# veils_v110.net
KiCad netlist of a schematic drawn in EAGLE
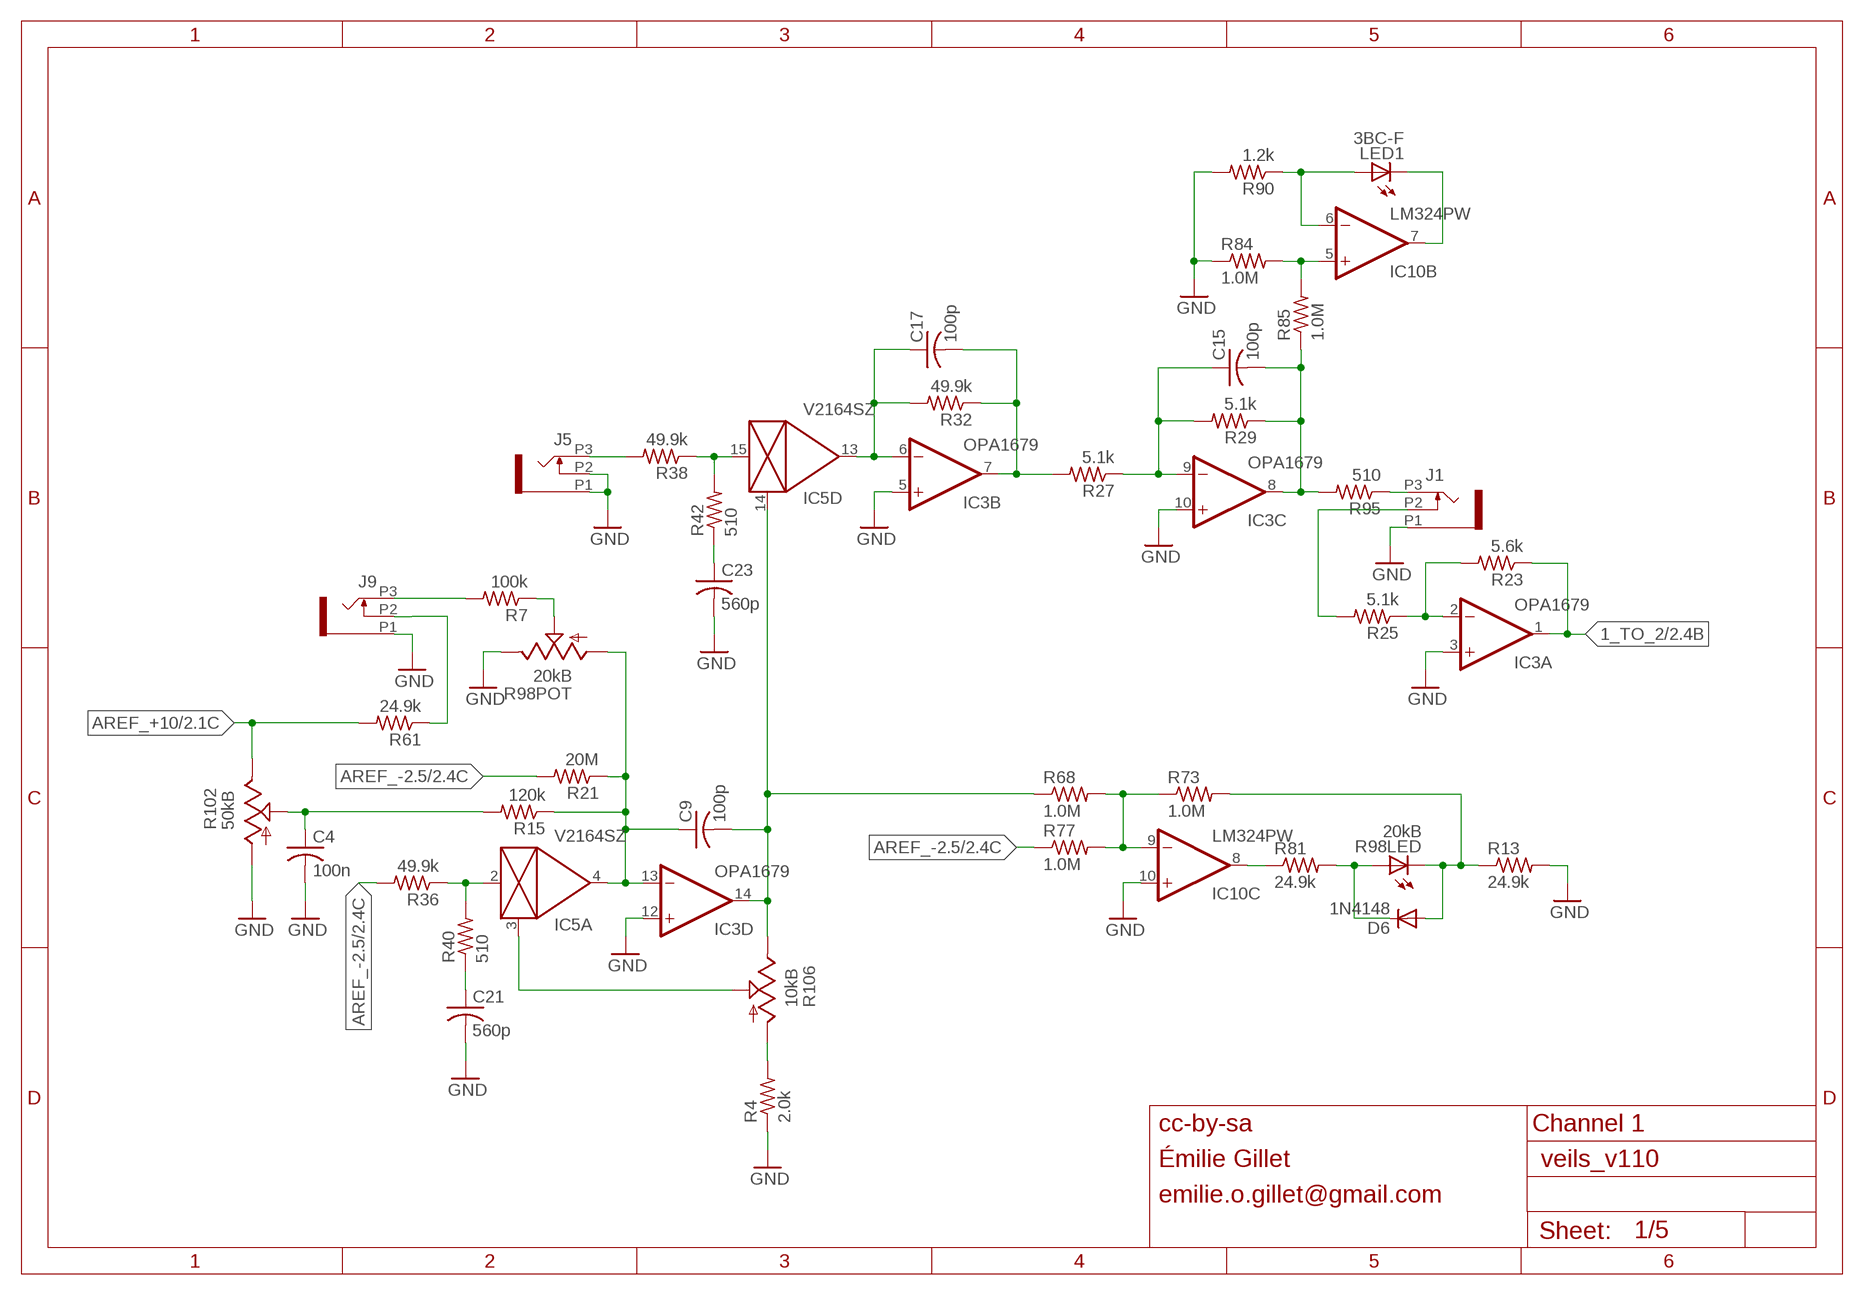
[diagram p0: schematic, sheet 1]
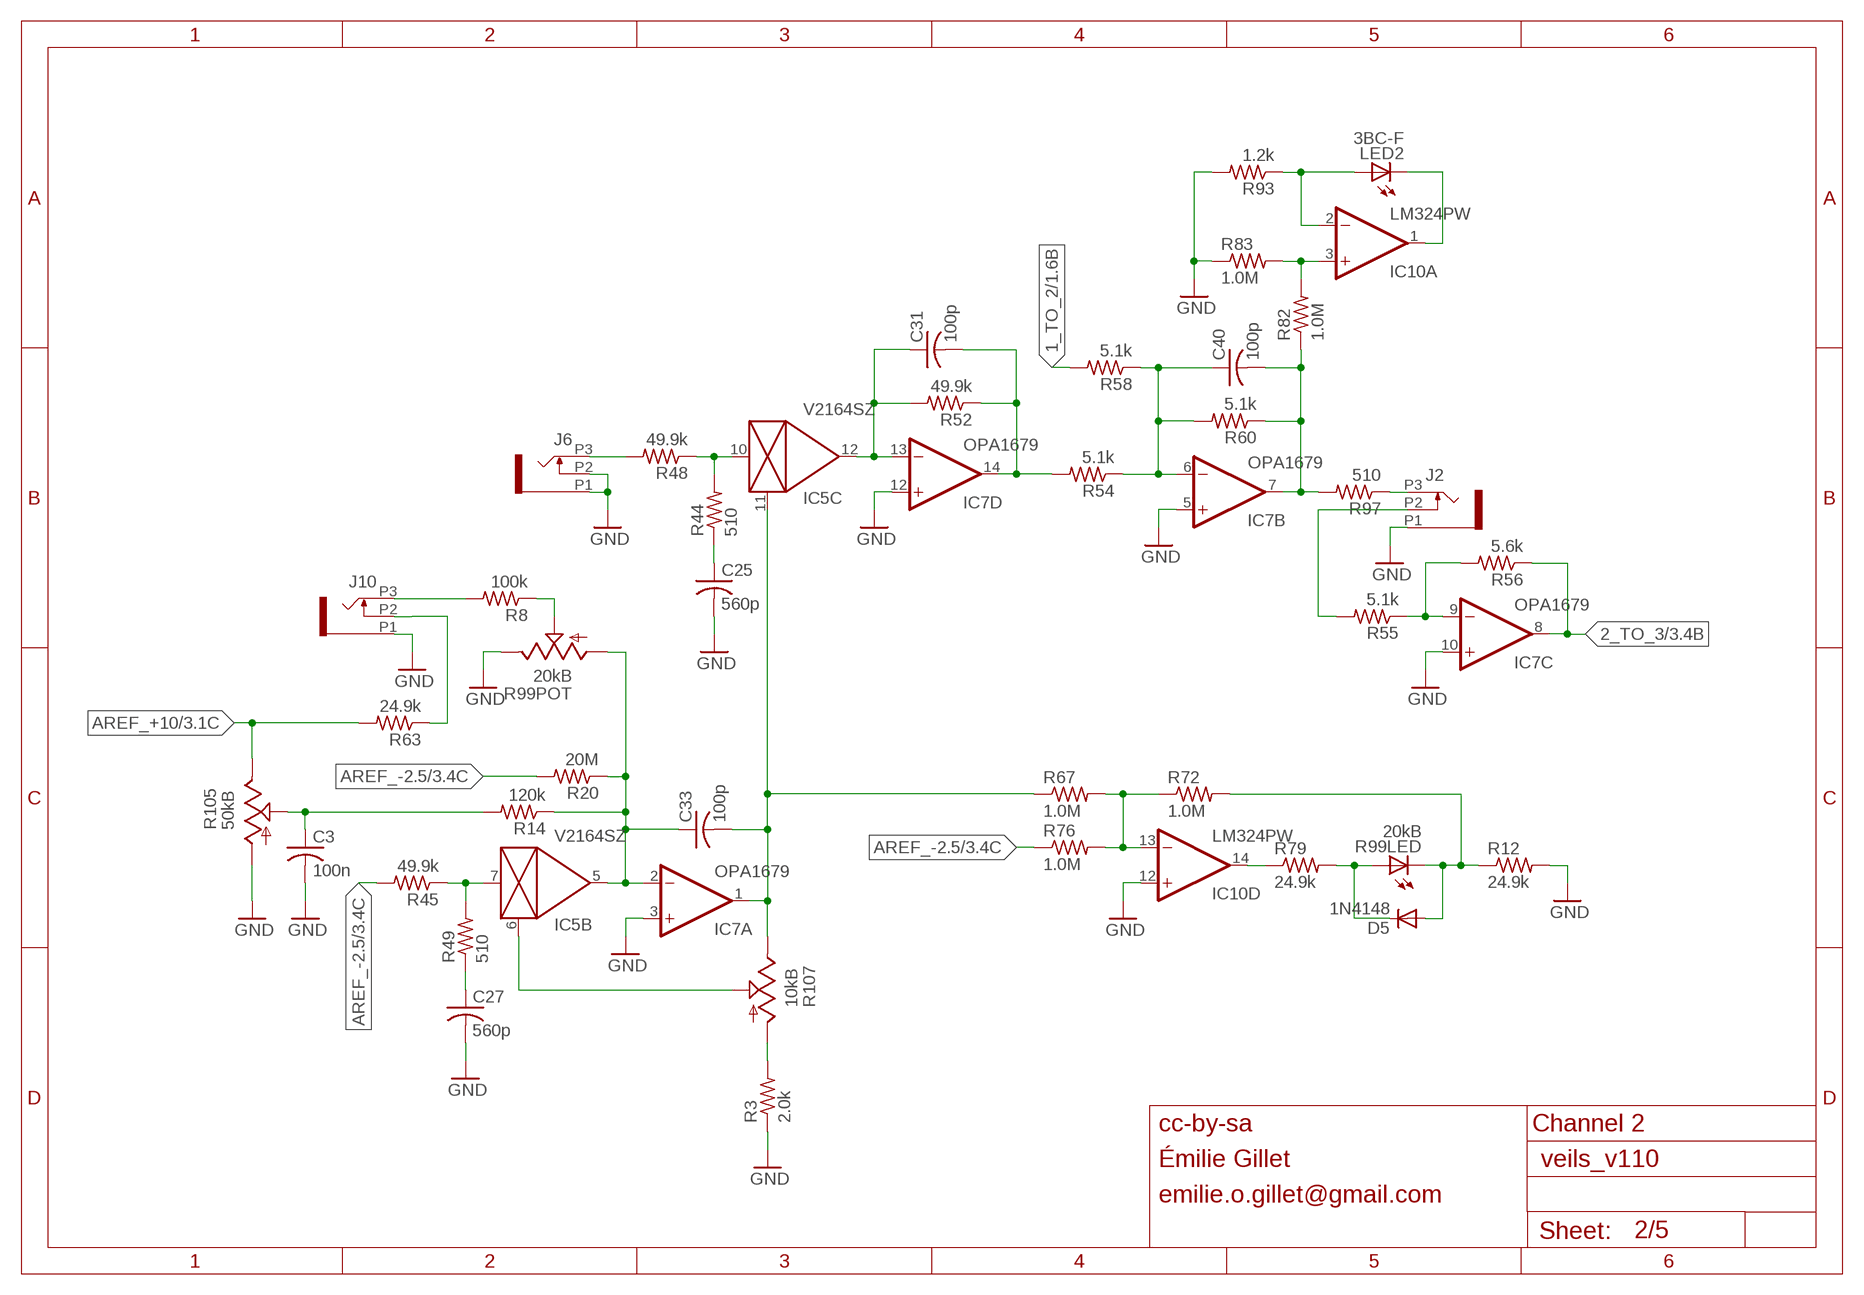
[diagram p1: schematic, sheet 2]
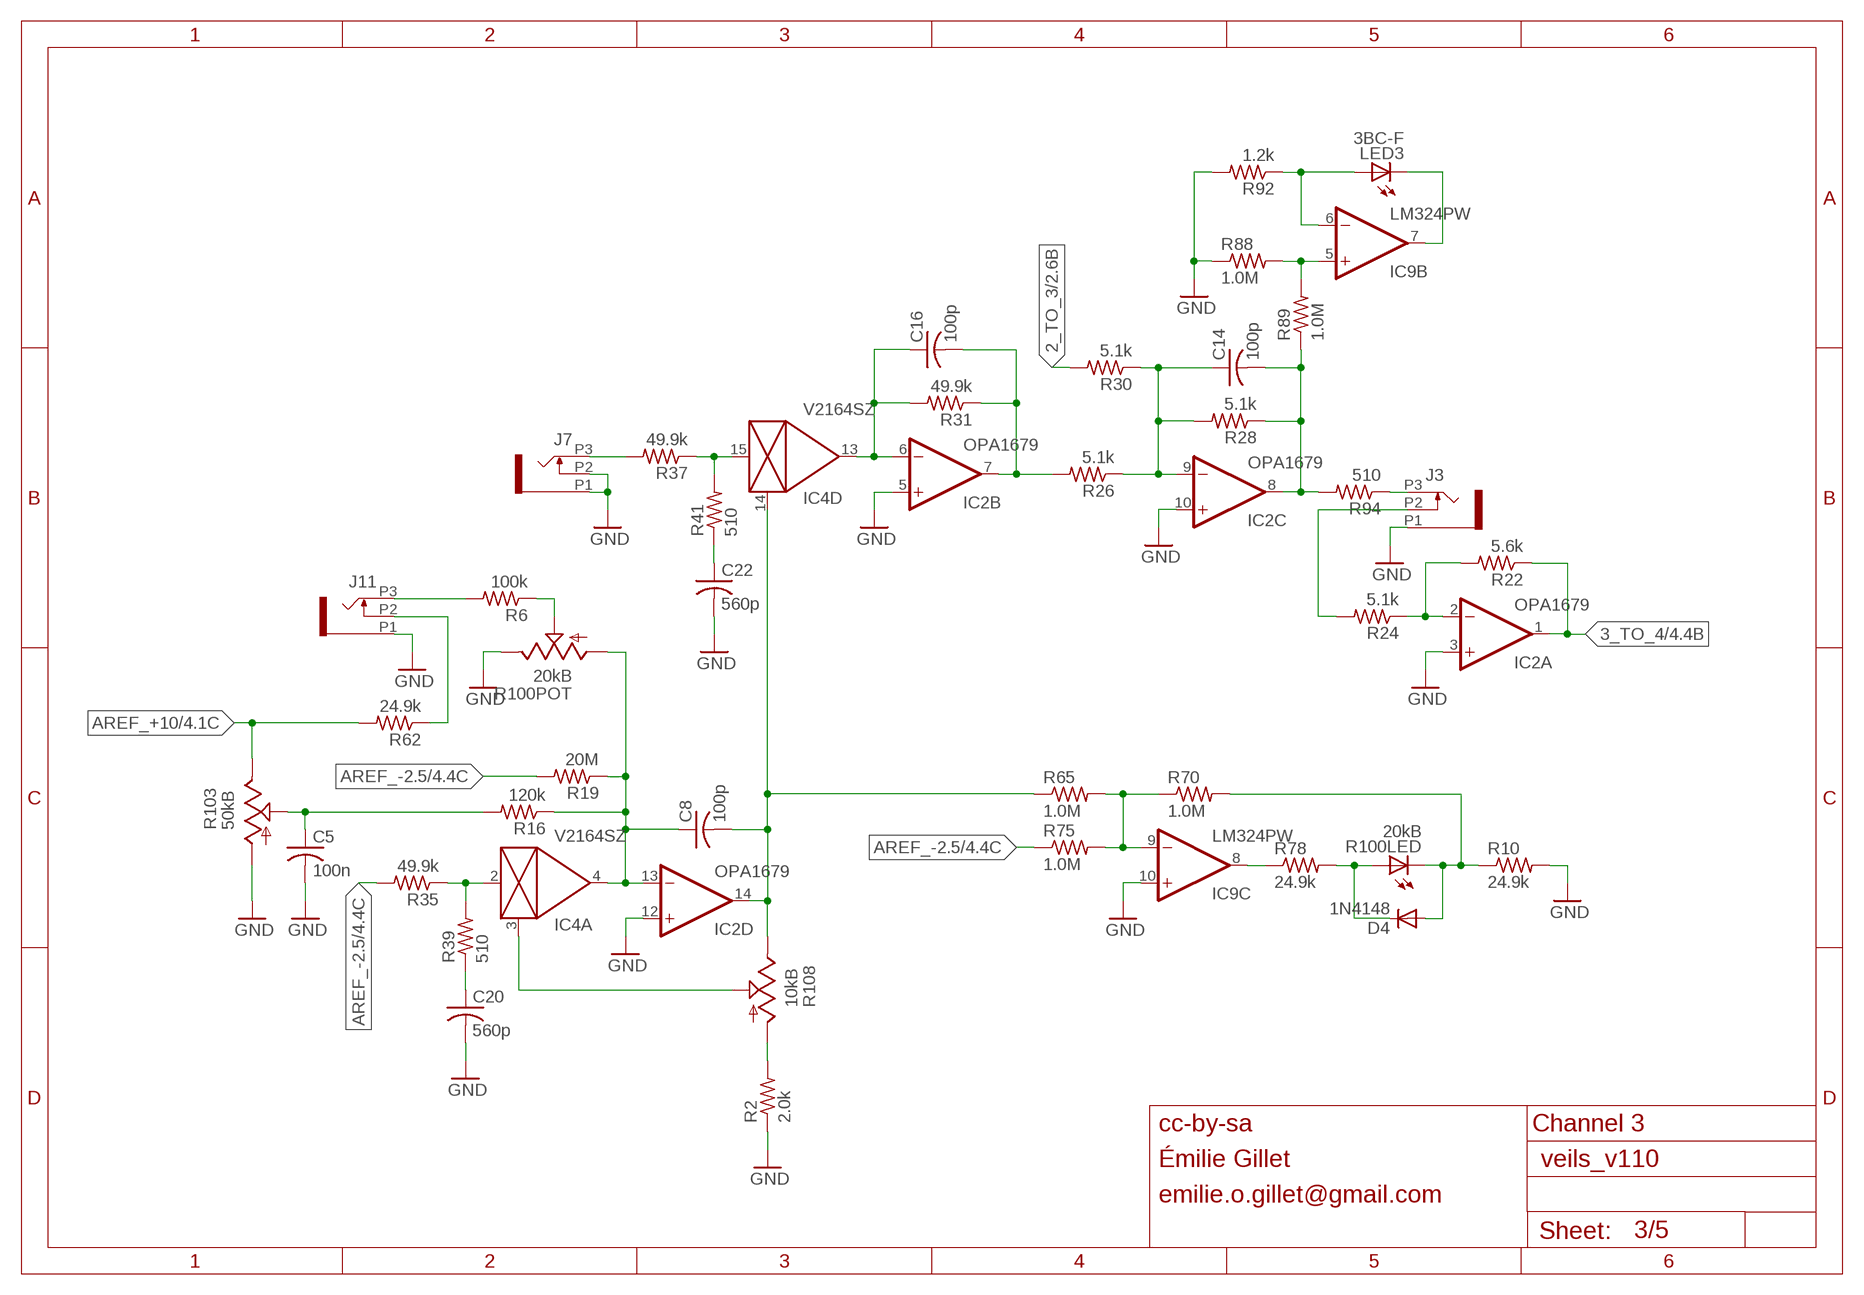
[diagram p2: schematic, sheet 3]
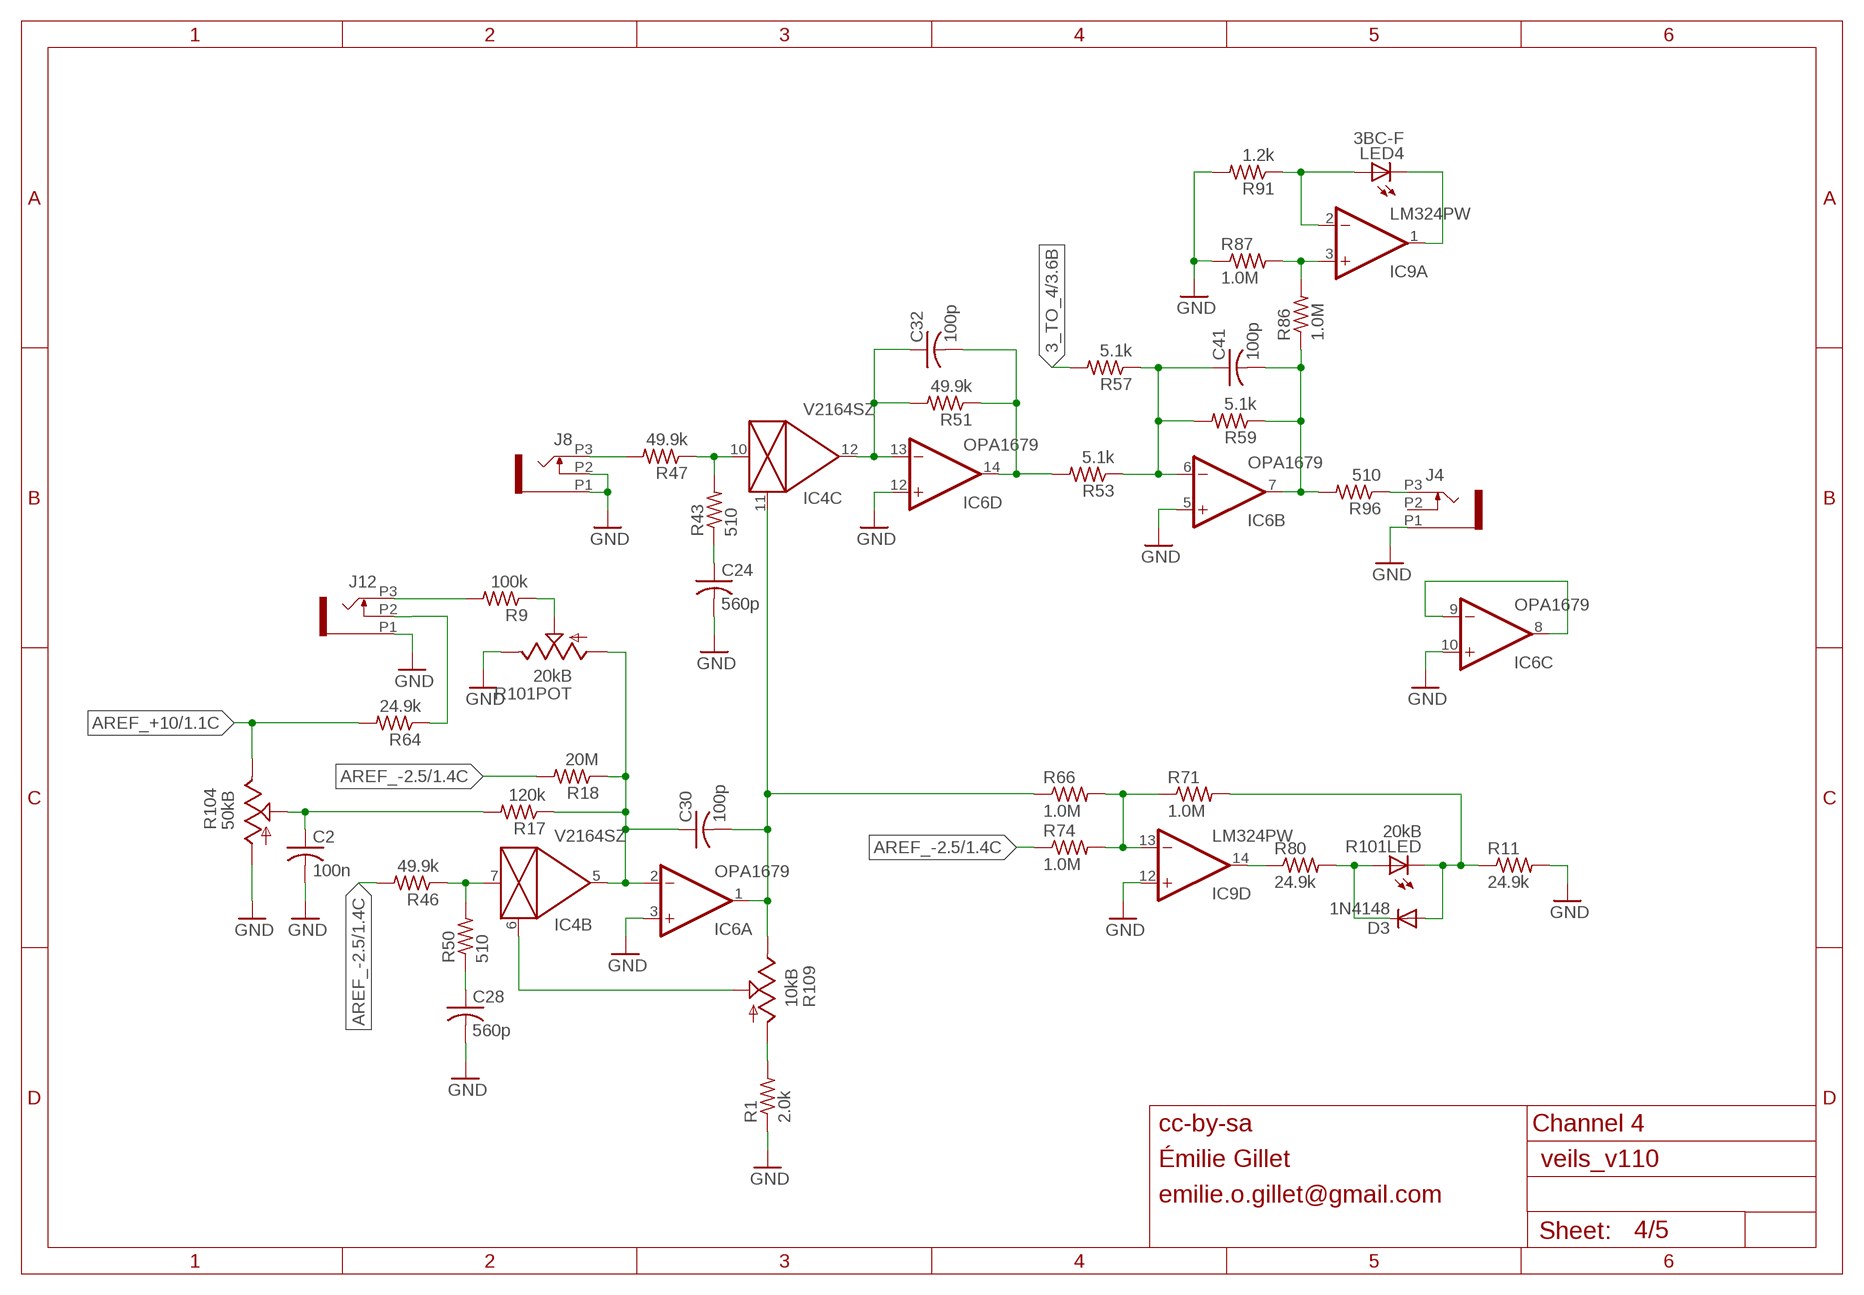
[diagram p3: schematic, sheet 4]
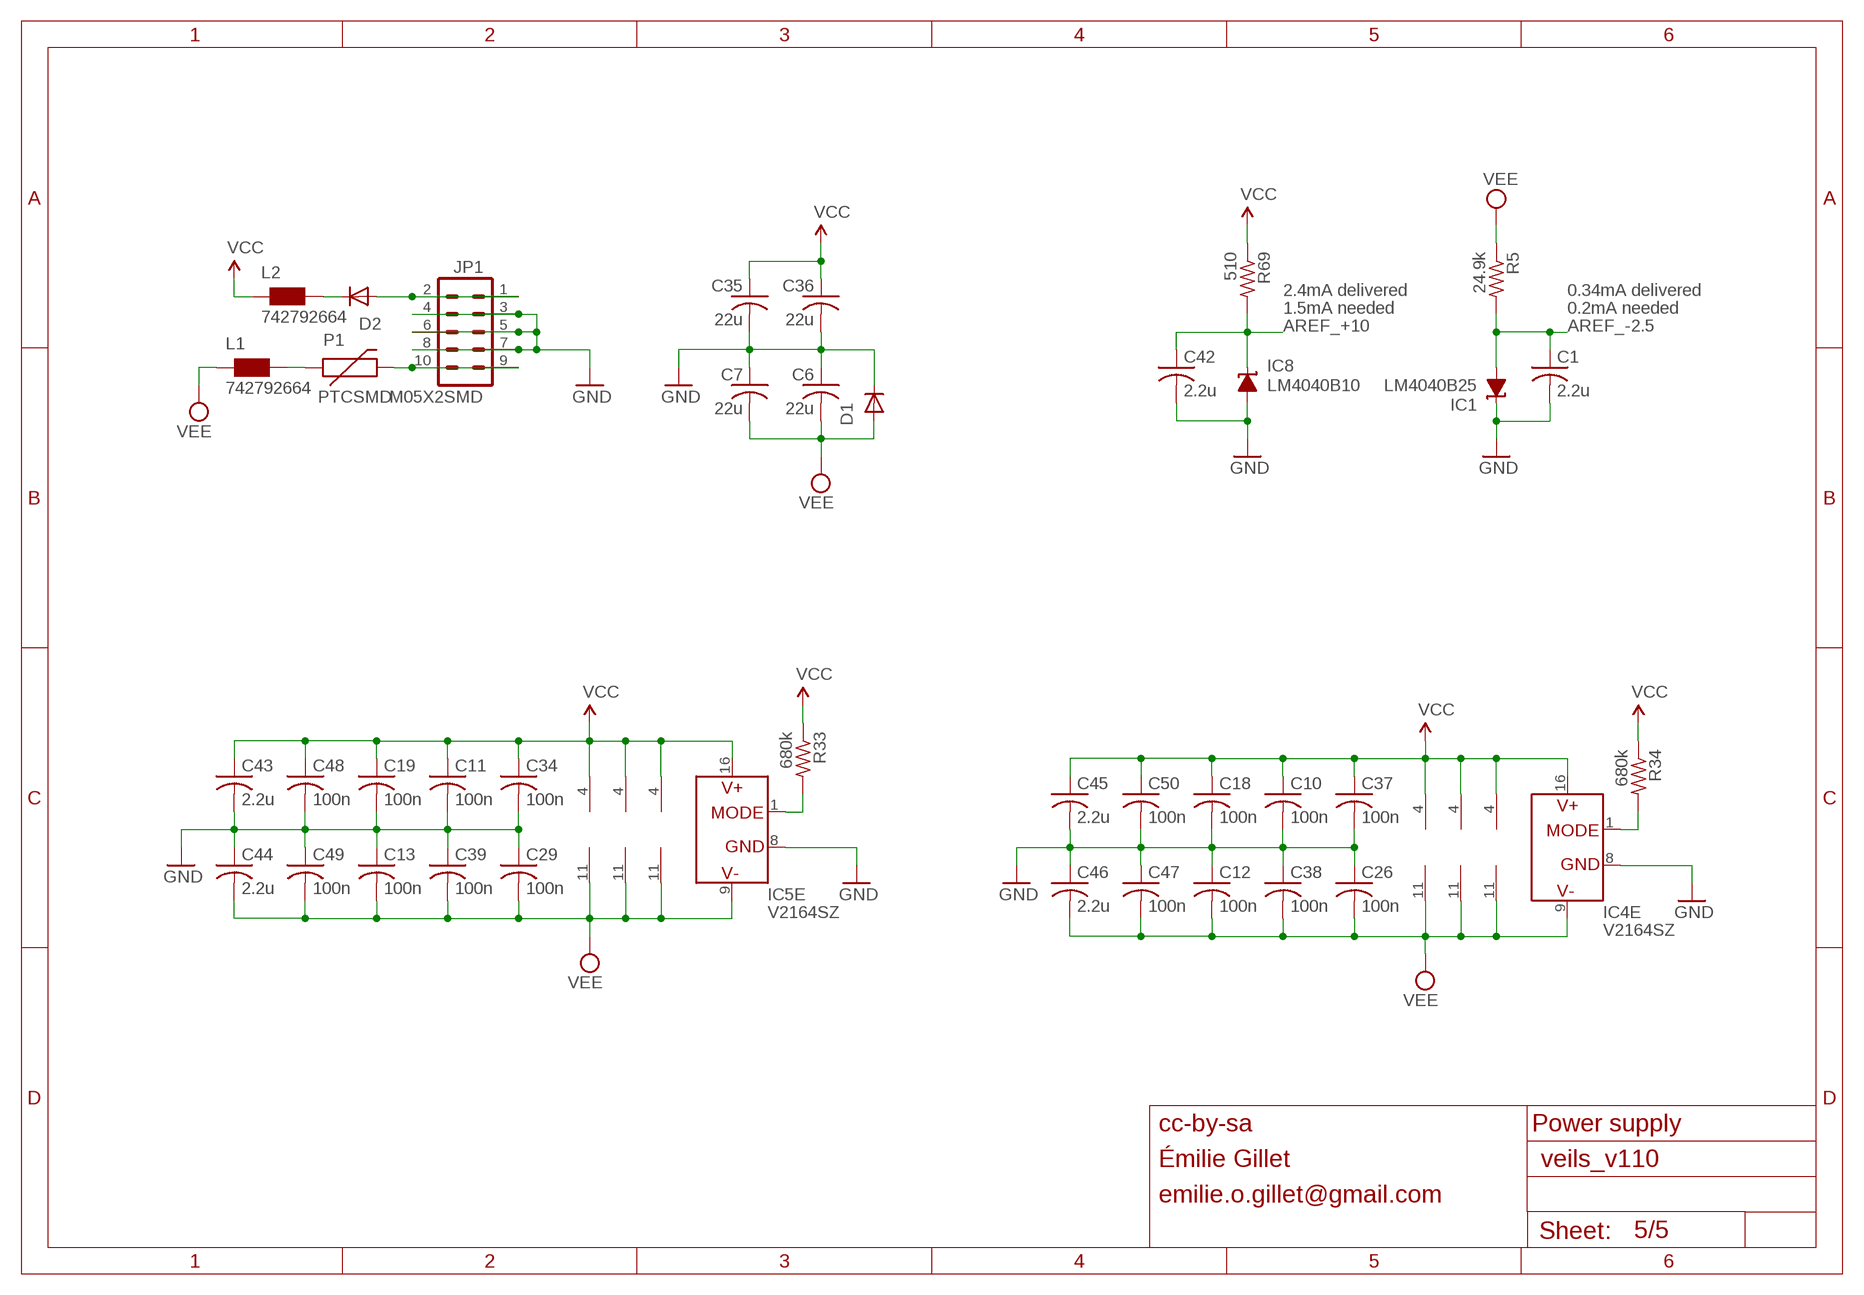
[diagram p4: schematic, sheet 5]

(export (version "E")
  (design (tool "Eeschema 10.0.6"))
  (components
    (comp (ref "C4")
      (value "100n")
      (footprint "eagle-import:C0402")
      (libsource (lib "eagle-import") (part "C-USC0402"))
    )
    (comp (ref "C9")
      (value "100p")
      (footprint "eagle-import:C0402")
      (libsource (lib "eagle-import") (part "C-USC0402"))
    )
    (comp (ref "C15")
      (value "100p")
      (footprint "eagle-import:C0402")
      (libsource (lib "eagle-import") (part "C-USC0402"))
    )
    (comp (ref "C17")
      (value "100p")
      (footprint "eagle-import:C0402")
      (libsource (lib "eagle-import") (part "C-USC0402"))
    )
    (comp (ref "C21")
      (value "560p")
      (footprint "eagle-import:C0402")
      (libsource (lib "eagle-import") (part "C-USC0402"))
    )
    (comp (ref "C23")
      (value "560p")
      (footprint "eagle-import:C0402")
      (libsource (lib "eagle-import") (part "C-USC0402"))
    )
    (comp (ref "D6")
      (value "1N4148")
      (footprint "eagle-import:SOD523")
      (libsource (lib "eagle-import") (part "DIODE-SOD523"))
    )
    (comp (ref "IC3")
      (value "OPA1679")
      (footprint "eagle-import:TSSOP14_065")
      (libsource (lib "eagle-import") (part "OPA1679PW"))
    )
    (comp (ref "IC5")
      (value "V2164SZ")
      (footprint "eagle-import:SOIC16N")
      (libsource (lib "eagle-import") (part "SSM2164S"))
    )
    (comp (ref "IC10")
      (value "LM324PW")
      (footprint "eagle-import:TSSOP14_065")
      (libsource (lib "eagle-import") (part "TL074PW"))
    )
    (comp (ref "J1")
      (value "PJ301_THONKICONNTME")
      (footprint "eagle-import:WQP_PJ_301M_TME")
      (libsource (lib "eagle-import") (part "PJ301_THONKICONNTME"))
    )
    (comp (ref "J5")
      (value "PJ301_THONKICONNTME")
      (footprint "eagle-import:WQP_PJ_301M_TME")
      (libsource (lib "eagle-import") (part "PJ301_THONKICONNTME"))
    )
    (comp (ref "J9")
      (value "PJ301_THONKICONNTME")
      (footprint "eagle-import:WQP_PJ_301M_TME")
      (libsource (lib "eagle-import") (part "PJ301_THONKICONNTME"))
    )
    (comp (ref "LED1")
      (value "3BC-F")
      (footprint "eagle-import:LED3MM")
      (libsource (lib "eagle-import") (part "LED3MM"))
    )
    (comp (ref "R4")
      (value "2.0k")
      (footprint "eagle-import:R0402")
      (libsource (lib "eagle-import") (part "R-US_R0402"))
    )
    (comp (ref "R7")
      (value "100k")
      (footprint "eagle-import:R0402")
      (libsource (lib "eagle-import") (part "R-US_R0402"))
    )
    (comp (ref "R13")
      (value "24.9k")
      (footprint "eagle-import:R0402")
      (libsource (lib "eagle-import") (part "R-US_R0402"))
    )
    (comp (ref "R15")
      (value "120k")
      (footprint "eagle-import:R0402")
      (libsource (lib "eagle-import") (part "R-US_R0402"))
    )
    (comp (ref "R21")
      (value "20M")
      (footprint "eagle-import:R0402")
      (libsource (lib "eagle-import") (part "R-US_R0402"))
    )
    (comp (ref "R23")
      (value "5.6k")
      (footprint "eagle-import:R0402")
      (libsource (lib "eagle-import") (part "R-US_R0402"))
    )
    (comp (ref "R25")
      (value "5.1k")
      (footprint "eagle-import:R0402")
      (libsource (lib "eagle-import") (part "R-US_R0402"))
    )
    (comp (ref "R27")
      (value "5.1k")
      (footprint "eagle-import:R0402")
      (libsource (lib "eagle-import") (part "R-US_R0402"))
    )
    (comp (ref "R29")
      (value "5.1k")
      (footprint "eagle-import:R0402")
      (libsource (lib "eagle-import") (part "R-US_R0402"))
    )
    (comp (ref "R32")
      (value "49.9k")
      (footprint "eagle-import:R0402")
      (libsource (lib "eagle-import") (part "R-US_R0402"))
    )
    (comp (ref "R36")
      (value "49.9k")
      (footprint "eagle-import:R0402")
      (libsource (lib "eagle-import") (part "R-US_R0402"))
    )
    (comp (ref "R38")
      (value "49.9k")
      (footprint "eagle-import:R0402")
      (libsource (lib "eagle-import") (part "R-US_R0402"))
    )
    (comp (ref "R40")
      (value "510")
      (footprint "eagle-import:R0402")
      (libsource (lib "eagle-import") (part "R-US_R0402"))
    )
    (comp (ref "R42")
      (value "510")
      (footprint "eagle-import:R0402")
      (libsource (lib "eagle-import") (part "R-US_R0402"))
    )
    (comp (ref "R61")
      (value "24.9k")
      (footprint "eagle-import:R0402")
      (libsource (lib "eagle-import") (part "R-US_R0402"))
    )
    (comp (ref "R68")
      (value "1.0M")
      (footprint "eagle-import:R0402")
      (libsource (lib "eagle-import") (part "R-US_R0402"))
    )
    (comp (ref "R73")
      (value "1.0M")
      (footprint "eagle-import:R0402")
      (libsource (lib "eagle-import") (part "R-US_R0402"))
    )
    (comp (ref "R77")
      (value "1.0M")
      (footprint "eagle-import:R0402")
      (libsource (lib "eagle-import") (part "R-US_R0402"))
    )
    (comp (ref "R81")
      (value "24.9k")
      (footprint "eagle-import:R0402")
      (libsource (lib "eagle-import") (part "R-US_R0402"))
    )
    (comp (ref "R84")
      (value "1.0M")
      (footprint "eagle-import:R0402")
      (libsource (lib "eagle-import") (part "R-US_R0402"))
    )
    (comp (ref "R85")
      (value "1.0M")
      (footprint "eagle-import:R0402")
      (libsource (lib "eagle-import") (part "R-US_R0402"))
    )
    (comp (ref "R90")
      (value "1.2k")
      (footprint "eagle-import:R0402")
      (libsource (lib "eagle-import") (part "R-US_R0402"))
    )
    (comp (ref "R95")
      (value "510")
      (footprint "eagle-import:R0603")
      (libsource (lib "eagle-import") (part "R-US_R0603"))
    )
    (comp (ref "R98")
      (value "20kB")
      (footprint "eagle-import:BOURNS_SLIDER")
      (libsource (lib "eagle-import") (part "BOURNS_SLIDER"))
    )
    (comp (ref "R102")
      (value "50kB")
      (footprint "eagle-import:ALPS_POT_NARROW")
      (libsource (lib "eagle-import") (part "POT_USVERTICAL_NARROW"))
    )
    (comp (ref "R106")
      (value "10kB")
      (footprint "eagle-import:ALPS_POT_NARROW")
      (libsource (lib "eagle-import") (part "POT_USVERTICAL_NARROW"))
    )
    (comp (ref "C1")
      (value "2.2u")
      (footprint "eagle-import:C0603")
      (libsource (lib "eagle-import") (part "C-USC0603"))
    )
    (comp (ref "C6")
      (value "22u")
      (footprint "eagle-import:C1206")
      (libsource (lib "eagle-import") (part "C-USC1206"))
    )
    (comp (ref "C7")
      (value "22u")
      (footprint "eagle-import:C1206")
      (libsource (lib "eagle-import") (part "C-USC1206"))
    )
    (comp (ref "C10")
      (value "100n")
      (footprint "eagle-import:C0402")
      (libsource (lib "eagle-import") (part "C-USC0402"))
    )
    (comp (ref "C11")
      (value "100n")
      (footprint "eagle-import:C0402")
      (libsource (lib "eagle-import") (part "C-USC0402"))
    )
    (comp (ref "C12")
      (value "100n")
      (footprint "eagle-import:C0402")
      (libsource (lib "eagle-import") (part "C-USC0402"))
    )
    (comp (ref "C13")
      (value "100n")
      (footprint "eagle-import:C0402")
      (libsource (lib "eagle-import") (part "C-USC0402"))
    )
    (comp (ref "C18")
      (value "100n")
      (footprint "eagle-import:C0402")
      (libsource (lib "eagle-import") (part "C-USC0402"))
    )
    (comp (ref "C19")
      (value "100n")
      (footprint "eagle-import:C0402")
      (libsource (lib "eagle-import") (part "C-USC0402"))
    )
    (comp (ref "C26")
      (value "100n")
      (footprint "eagle-import:C0402")
      (libsource (lib "eagle-import") (part "C-USC0402"))
    )
    (comp (ref "C29")
      (value "100n")
      (footprint "eagle-import:C0402")
      (libsource (lib "eagle-import") (part "C-USC0402"))
    )
    (comp (ref "C34")
      (value "100n")
      (footprint "eagle-import:C0402")
      (libsource (lib "eagle-import") (part "C-USC0402"))
    )
    (comp (ref "C35")
      (value "22u")
      (footprint "eagle-import:C1206")
      (libsource (lib "eagle-import") (part "C-USC1206"))
    )
    (comp (ref "C36")
      (value "22u")
      (footprint "eagle-import:C1206")
      (libsource (lib "eagle-import") (part "C-USC1206"))
    )
    (comp (ref "C37")
      (value "100n")
      (footprint "eagle-import:C0402")
      (libsource (lib "eagle-import") (part "C-USC0402"))
    )
    (comp (ref "C38")
      (value "100n")
      (footprint "eagle-import:C0402")
      (libsource (lib "eagle-import") (part "C-USC0402"))
    )
    (comp (ref "C39")
      (value "100n")
      (footprint "eagle-import:C0402")
      (libsource (lib "eagle-import") (part "C-USC0402"))
    )
    (comp (ref "C42")
      (value "2.2u")
      (footprint "eagle-import:C0603")
      (libsource (lib "eagle-import") (part "C-USC0603"))
    )
    (comp (ref "C43")
      (value "2.2u")
      (footprint "eagle-import:C0603")
      (libsource (lib "eagle-import") (part "C-USC0603"))
    )
    (comp (ref "C44")
      (value "2.2u")
      (footprint "eagle-import:C0603")
      (libsource (lib "eagle-import") (part "C-USC0603"))
    )
    (comp (ref "C45")
      (value "2.2u")
      (footprint "eagle-import:C0603")
      (libsource (lib "eagle-import") (part "C-USC0603"))
    )
    (comp (ref "C46")
      (value "2.2u")
      (footprint "eagle-import:C0603")
      (libsource (lib "eagle-import") (part "C-USC0603"))
    )
    (comp (ref "C47")
      (value "100n")
      (footprint "eagle-import:C0402")
      (libsource (lib "eagle-import") (part "C-USC0402"))
    )
    (comp (ref "C48")
      (value "100n")
      (footprint "eagle-import:C0402")
      (libsource (lib "eagle-import") (part "C-USC0402"))
    )
    (comp (ref "C49")
      (value "100n")
      (footprint "eagle-import:C0402")
      (libsource (lib "eagle-import") (part "C-USC0402"))
    )
    (comp (ref "C50")
      (value "100n")
      (footprint "eagle-import:C0402")
      (libsource (lib "eagle-import") (part "C-USC0402"))
    )
    (comp (ref "D1")
      (value "1N5819HW")
      (footprint "eagle-import:SOD123")
      (libsource (lib "eagle-import") (part "DIODE-SOD123"))
    )
    (comp (ref "D2")
      (value "1N5819HW")
      (footprint "eagle-import:SOD123")
      (libsource (lib "eagle-import") (part "DIODE-SOD123"))
    )
    (comp (ref "IC1")
      (value "LM4040B25")
      (footprint "eagle-import:DBZ_R-PDSO-G3")
      (libsource (lib "eagle-import") (part "LM4041DBZB12"))
    )
    (comp (ref "IC2")
      (value "OPA1679")
      (footprint "eagle-import:TSSOP14_065")
      (libsource (lib "eagle-import") (part "OPA1679PW"))
    )
    (comp (ref "IC4")
      (value "V2164SZ")
      (footprint "eagle-import:SOIC16N")
      (libsource (lib "eagle-import") (part "SSM2164S"))
    )
    (comp (ref "IC6")
      (value "OPA1679")
      (footprint "eagle-import:TSSOP14_065")
      (libsource (lib "eagle-import") (part "OPA1679PW"))
    )
    (comp (ref "IC7")
      (value "OPA1679")
      (footprint "eagle-import:TSSOP14_065")
      (libsource (lib "eagle-import") (part "OPA1679PW"))
    )
    (comp (ref "IC8")
      (value "LM4040B10")
      (footprint "eagle-import:DBZ_R-PDSO-G3")
      (libsource (lib "eagle-import") (part "LM4041DBZB12"))
    )
    (comp (ref "IC9")
      (value "LM324PW")
      (footprint "eagle-import:TSSOP14_065")
      (libsource (lib "eagle-import") (part "TL074PW"))
    )
    (comp (ref "JP1")
      (value "M05X2SMD")
      (footprint "eagle-import:2X5-SMD")
      (libsource (lib "eagle-import") (part "M05X2SMD"))
    )
    (comp (ref "L1")
      (value "742792664")
      (footprint "eagle-import:0603")
      (libsource (lib "eagle-import") (part "WE-CBF_0603"))
    )
    (comp (ref "L2")
      (value "742792664")
      (footprint "eagle-import:0603")
      (libsource (lib "eagle-import") (part "WE-CBF_0603"))
    )
    (comp (ref "P1")
      (value "PTCSMD")
      (footprint "eagle-import:PTC-1206")
      (libsource (lib "eagle-import") (part "PTCSMD"))
    )
    (comp (ref "R5")
      (value "24.9k")
      (footprint "eagle-import:R0402")
      (libsource (lib "eagle-import") (part "R-US_R0402"))
    )
    (comp (ref "R33")
      (value "680k")
      (footprint "eagle-import:R0402")
      (libsource (lib "eagle-import") (part "R-US_R0402"))
    )
    (comp (ref "R34")
      (value "680k")
      (footprint "eagle-import:R0402")
      (libsource (lib "eagle-import") (part "R-US_R0402"))
    )
    (comp (ref "R69")
      (value "510")
      (footprint "eagle-import:R0402")
      (libsource (lib "eagle-import") (part "R-US_R0402"))
    )
    (comp (ref "C3")
      (value "100n")
      (footprint "eagle-import:C0402")
      (libsource (lib "eagle-import") (part "C-USC0402"))
    )
    (comp (ref "C25")
      (value "560p")
      (footprint "eagle-import:C0402")
      (libsource (lib "eagle-import") (part "C-USC0402"))
    )
    (comp (ref "C27")
      (value "560p")
      (footprint "eagle-import:C0402")
      (libsource (lib "eagle-import") (part "C-USC0402"))
    )
    (comp (ref "C31")
      (value "100p")
      (footprint "eagle-import:C0402")
      (libsource (lib "eagle-import") (part "C-USC0402"))
    )
    (comp (ref "C33")
      (value "100p")
      (footprint "eagle-import:C0402")
      (libsource (lib "eagle-import") (part "C-USC0402"))
    )
    (comp (ref "C40")
      (value "100p")
      (footprint "eagle-import:C0402")
      (libsource (lib "eagle-import") (part "C-USC0402"))
    )
    (comp (ref "D5")
      (value "1N4148")
      (footprint "eagle-import:SOD523")
      (libsource (lib "eagle-import") (part "DIODE-SOD523"))
    )
    (comp (ref "J2")
      (value "PJ301_THONKICONNTME")
      (footprint "eagle-import:WQP_PJ_301M_TME")
      (libsource (lib "eagle-import") (part "PJ301_THONKICONNTME"))
    )
    (comp (ref "J6")
      (value "PJ301_THONKICONNTME")
      (footprint "eagle-import:WQP_PJ_301M_TME")
      (libsource (lib "eagle-import") (part "PJ301_THONKICONNTME"))
    )
    (comp (ref "J10")
      (value "PJ301_THONKICONNTME")
      (footprint "eagle-import:WQP_PJ_301M_TME")
      (libsource (lib "eagle-import") (part "PJ301_THONKICONNTME"))
    )
    (comp (ref "LED2")
      (value "3BC-F")
      (footprint "eagle-import:LED3MM")
      (libsource (lib "eagle-import") (part "LED3MM"))
    )
    (comp (ref "R3")
      (value "2.0k")
      (footprint "eagle-import:R0402")
      (libsource (lib "eagle-import") (part "R-US_R0402"))
    )
    (comp (ref "R8")
      (value "100k")
      (footprint "eagle-import:R0402")
      (libsource (lib "eagle-import") (part "R-US_R0402"))
    )
    (comp (ref "R12")
      (value "24.9k")
      (footprint "eagle-import:R0402")
      (libsource (lib "eagle-import") (part "R-US_R0402"))
    )
    (comp (ref "R14")
      (value "120k")
      (footprint "eagle-import:R0402")
      (libsource (lib "eagle-import") (part "R-US_R0402"))
    )
    (comp (ref "R20")
      (value "20M")
      (footprint "eagle-import:R0402")
      (libsource (lib "eagle-import") (part "R-US_R0402"))
    )
    (comp (ref "R44")
      (value "510")
      (footprint "eagle-import:R0402")
      (libsource (lib "eagle-import") (part "R-US_R0402"))
    )
    (comp (ref "R45")
      (value "49.9k")
      (footprint "eagle-import:R0402")
      (libsource (lib "eagle-import") (part "R-US_R0402"))
    )
    (comp (ref "R48")
      (value "49.9k")
      (footprint "eagle-import:R0402")
      (libsource (lib "eagle-import") (part "R-US_R0402"))
    )
    (comp (ref "R49")
      (value "510")
      (footprint "eagle-import:R0402")
      (libsource (lib "eagle-import") (part "R-US_R0402"))
    )
    (comp (ref "R52")
      (value "49.9k")
      (footprint "eagle-import:R0402")
      (libsource (lib "eagle-import") (part "R-US_R0402"))
    )
    (comp (ref "R54")
      (value "5.1k")
      (footprint "eagle-import:R0402")
      (libsource (lib "eagle-import") (part "R-US_R0402"))
    )
    (comp (ref "R55")
      (value "5.1k")
      (footprint "eagle-import:R0402")
      (libsource (lib "eagle-import") (part "R-US_R0402"))
    )
    (comp (ref "R56")
      (value "5.6k")
      (footprint "eagle-import:R0402")
      (libsource (lib "eagle-import") (part "R-US_R0402"))
    )
    (comp (ref "R58")
      (value "5.1k")
      (footprint "eagle-import:R0402")
      (libsource (lib "eagle-import") (part "R-US_R0402"))
    )
    (comp (ref "R60")
      (value "5.1k")
      (footprint "eagle-import:R0402")
      (libsource (lib "eagle-import") (part "R-US_R0402"))
    )
    (comp (ref "R63")
      (value "24.9k")
      (footprint "eagle-import:R0402")
      (libsource (lib "eagle-import") (part "R-US_R0402"))
    )
    (comp (ref "R67")
      (value "1.0M")
      (footprint "eagle-import:R0402")
      (libsource (lib "eagle-import") (part "R-US_R0402"))
    )
    (comp (ref "R72")
      (value "1.0M")
      (footprint "eagle-import:R0402")
      (libsource (lib "eagle-import") (part "R-US_R0402"))
    )
    (comp (ref "R76")
      (value "1.0M")
      (footprint "eagle-import:R0402")
      (libsource (lib "eagle-import") (part "R-US_R0402"))
    )
    (comp (ref "R79")
      (value "24.9k")
      (footprint "eagle-import:R0402")
      (libsource (lib "eagle-import") (part "R-US_R0402"))
    )
    (comp (ref "R82")
      (value "1.0M")
      (footprint "eagle-import:R0402")
      (libsource (lib "eagle-import") (part "R-US_R0402"))
    )
    (comp (ref "R83")
      (value "1.0M")
      (footprint "eagle-import:R0402")
      (libsource (lib "eagle-import") (part "R-US_R0402"))
    )
    (comp (ref "R93")
      (value "1.2k")
      (footprint "eagle-import:R0402")
      (libsource (lib "eagle-import") (part "R-US_R0402"))
    )
    (comp (ref "R97")
      (value "510")
      (footprint "eagle-import:R0603")
      (libsource (lib "eagle-import") (part "R-US_R0603"))
    )
    (comp (ref "R99")
      (value "20kB")
      (footprint "eagle-import:BOURNS_SLIDER")
      (libsource (lib "eagle-import") (part "BOURNS_SLIDER"))
    )
    (comp (ref "R105")
      (value "50kB")
      (footprint "eagle-import:ALPS_POT_NARROW")
      (libsource (lib "eagle-import") (part "POT_USVERTICAL_NARROW"))
    )
    (comp (ref "R107")
      (value "10kB")
      (footprint "eagle-import:ALPS_POT_NARROW")
      (libsource (lib "eagle-import") (part "POT_USVERTICAL_NARROW"))
    )
    (comp (ref "C5")
      (value "100n")
      (footprint "eagle-import:C0402")
      (libsource (lib "eagle-import") (part "C-USC0402"))
    )
    (comp (ref "C8")
      (value "100p")
      (footprint "eagle-import:C0402")
      (libsource (lib "eagle-import") (part "C-USC0402"))
    )
    (comp (ref "C14")
      (value "100p")
      (footprint "eagle-import:C0402")
      (libsource (lib "eagle-import") (part "C-USC0402"))
    )
    (comp (ref "C16")
      (value "100p")
      (footprint "eagle-import:C0402")
      (libsource (lib "eagle-import") (part "C-USC0402"))
    )
    (comp (ref "C20")
      (value "560p")
      (footprint "eagle-import:C0402")
      (libsource (lib "eagle-import") (part "C-USC0402"))
    )
    (comp (ref "C22")
      (value "560p")
      (footprint "eagle-import:C0402")
      (libsource (lib "eagle-import") (part "C-USC0402"))
    )
    (comp (ref "D4")
      (value "1N4148")
      (footprint "eagle-import:SOD523")
      (libsource (lib "eagle-import") (part "DIODE-SOD523"))
    )
    (comp (ref "J3")
      (value "PJ301_THONKICONNTME")
      (footprint "eagle-import:WQP_PJ_301M_TME")
      (libsource (lib "eagle-import") (part "PJ301_THONKICONNTME"))
    )
    (comp (ref "J7")
      (value "PJ301_THONKICONNTME")
      (footprint "eagle-import:WQP_PJ_301M_TME")
      (libsource (lib "eagle-import") (part "PJ301_THONKICONNTME"))
    )
    (comp (ref "J11")
      (value "PJ301_THONKICONNTME")
      (footprint "eagle-import:WQP_PJ_301M_TME")
      (libsource (lib "eagle-import") (part "PJ301_THONKICONNTME"))
    )
    (comp (ref "LED3")
      (value "3BC-F")
      (footprint "eagle-import:LED3MM")
      (libsource (lib "eagle-import") (part "LED3MM"))
    )
    (comp (ref "R2")
      (value "2.0k")
      (footprint "eagle-import:R0402")
      (libsource (lib "eagle-import") (part "R-US_R0402"))
    )
    (comp (ref "R6")
      (value "100k")
      (footprint "eagle-import:R0402")
      (libsource (lib "eagle-import") (part "R-US_R0402"))
    )
    (comp (ref "R10")
      (value "24.9k")
      (footprint "eagle-import:R0402")
      (libsource (lib "eagle-import") (part "R-US_R0402"))
    )
    (comp (ref "R16")
      (value "120k")
      (footprint "eagle-import:R0402")
      (libsource (lib "eagle-import") (part "R-US_R0402"))
    )
    (comp (ref "R19")
      (value "20M")
      (footprint "eagle-import:R0402")
      (libsource (lib "eagle-import") (part "R-US_R0402"))
    )
    (comp (ref "R22")
      (value "5.6k")
      (footprint "eagle-import:R0402")
      (libsource (lib "eagle-import") (part "R-US_R0402"))
    )
    (comp (ref "R24")
      (value "5.1k")
      (footprint "eagle-import:R0402")
      (libsource (lib "eagle-import") (part "R-US_R0402"))
    )
    (comp (ref "R26")
      (value "5.1k")
      (footprint "eagle-import:R0402")
      (libsource (lib "eagle-import") (part "R-US_R0402"))
    )
    (comp (ref "R28")
      (value "5.1k")
      (footprint "eagle-import:R0402")
      (libsource (lib "eagle-import") (part "R-US_R0402"))
    )
    (comp (ref "R30")
      (value "5.1k")
      (footprint "eagle-import:R0402")
      (libsource (lib "eagle-import") (part "R-US_R0402"))
    )
    (comp (ref "R31")
      (value "49.9k")
      (footprint "eagle-import:R0402")
      (libsource (lib "eagle-import") (part "R-US_R0402"))
    )
    (comp (ref "R35")
      (value "49.9k")
      (footprint "eagle-import:R0402")
      (libsource (lib "eagle-import") (part "R-US_R0402"))
    )
    (comp (ref "R37")
      (value "49.9k")
      (footprint "eagle-import:R0402")
      (libsource (lib "eagle-import") (part "R-US_R0402"))
    )
    (comp (ref "R39")
      (value "510")
      (footprint "eagle-import:R0402")
      (libsource (lib "eagle-import") (part "R-US_R0402"))
    )
    (comp (ref "R41")
      (value "510")
      (footprint "eagle-import:R0402")
      (libsource (lib "eagle-import") (part "R-US_R0402"))
    )
    (comp (ref "R62")
      (value "24.9k")
      (footprint "eagle-import:R0402")
      (libsource (lib "eagle-import") (part "R-US_R0402"))
    )
    (comp (ref "R65")
      (value "1.0M")
      (footprint "eagle-import:R0402")
      (libsource (lib "eagle-import") (part "R-US_R0402"))
    )
    (comp (ref "R70")
      (value "1.0M")
      (footprint "eagle-import:R0402")
      (libsource (lib "eagle-import") (part "R-US_R0402"))
    )
    (comp (ref "R75")
      (value "1.0M")
      (footprint "eagle-import:R0402")
      (libsource (lib "eagle-import") (part "R-US_R0402"))
    )
    (comp (ref "R78")
      (value "24.9k")
      (footprint "eagle-import:R0402")
      (libsource (lib "eagle-import") (part "R-US_R0402"))
    )
    (comp (ref "R88")
      (value "1.0M")
      (footprint "eagle-import:R0402")
      (libsource (lib "eagle-import") (part "R-US_R0402"))
    )
    (comp (ref "R89")
      (value "1.0M")
      (footprint "eagle-import:R0402")
      (libsource (lib "eagle-import") (part "R-US_R0402"))
    )
    (comp (ref "R92")
      (value "1.2k")
      (footprint "eagle-import:R0402")
      (libsource (lib "eagle-import") (part "R-US_R0402"))
    )
    (comp (ref "R94")
      (value "510")
      (footprint "eagle-import:R0603")
      (libsource (lib "eagle-import") (part "R-US_R0603"))
    )
    (comp (ref "R100")
      (value "20kB")
      (footprint "eagle-import:BOURNS_SLIDER")
      (libsource (lib "eagle-import") (part "BOURNS_SLIDER"))
    )
    (comp (ref "R103")
      (value "50kB")
      (footprint "eagle-import:ALPS_POT_NARROW")
      (libsource (lib "eagle-import") (part "POT_USVERTICAL_NARROW"))
    )
    (comp (ref "R108")
      (value "10kB")
      (footprint "eagle-import:ALPS_POT_NARROW")
      (libsource (lib "eagle-import") (part "POT_USVERTICAL_NARROW"))
    )
    (comp (ref "C2")
      (value "100n")
      (footprint "eagle-import:C0402")
      (libsource (lib "eagle-import") (part "C-USC0402"))
    )
    (comp (ref "C24")
      (value "560p")
      (footprint "eagle-import:C0402")
      (libsource (lib "eagle-import") (part "C-USC0402"))
    )
    (comp (ref "C28")
      (value "560p")
      (footprint "eagle-import:C0402")
      (libsource (lib "eagle-import") (part "C-USC0402"))
    )
    (comp (ref "C30")
      (value "100p")
      (footprint "eagle-import:C0402")
      (libsource (lib "eagle-import") (part "C-USC0402"))
    )
    (comp (ref "C32")
      (value "100p")
      (footprint "eagle-import:C0402")
      (libsource (lib "eagle-import") (part "C-USC0402"))
    )
    (comp (ref "C41")
      (value "100p")
      (footprint "eagle-import:C0402")
      (libsource (lib "eagle-import") (part "C-USC0402"))
    )
    (comp (ref "D3")
      (value "1N4148")
      (footprint "eagle-import:SOD523")
      (libsource (lib "eagle-import") (part "DIODE-SOD523"))
    )
    (comp (ref "J4")
      (value "PJ301_THONKICONNTME")
      (footprint "eagle-import:WQP_PJ_301M_TME")
      (libsource (lib "eagle-import") (part "PJ301_THONKICONNTME"))
    )
    (comp (ref "J8")
      (value "PJ301_THONKICONNTME")
      (footprint "eagle-import:WQP_PJ_301M_TME")
      (libsource (lib "eagle-import") (part "PJ301_THONKICONNTME"))
    )
    (comp (ref "J12")
      (value "PJ301_THONKICONNTME")
      (footprint "eagle-import:WQP_PJ_301M_TME")
      (libsource (lib "eagle-import") (part "PJ301_THONKICONNTME"))
    )
    (comp (ref "LED4")
      (value "3BC-F")
      (footprint "eagle-import:LED3MM")
      (libsource (lib "eagle-import") (part "LED3MM"))
    )
    (comp (ref "R1")
      (value "2.0k")
      (footprint "eagle-import:R0402")
      (libsource (lib "eagle-import") (part "R-US_R0402"))
    )
    (comp (ref "R9")
      (value "100k")
      (footprint "eagle-import:R0402")
      (libsource (lib "eagle-import") (part "R-US_R0402"))
    )
    (comp (ref "R11")
      (value "24.9k")
      (footprint "eagle-import:R0402")
      (libsource (lib "eagle-import") (part "R-US_R0402"))
    )
    (comp (ref "R17")
      (value "120k")
      (footprint "eagle-import:R0402")
      (libsource (lib "eagle-import") (part "R-US_R0402"))
    )
    (comp (ref "R18")
      (value "20M")
      (footprint "eagle-import:R0402")
      (libsource (lib "eagle-import") (part "R-US_R0402"))
    )
    (comp (ref "R43")
      (value "510")
      (footprint "eagle-import:R0402")
      (libsource (lib "eagle-import") (part "R-US_R0402"))
    )
    (comp (ref "R46")
      (value "49.9k")
      (footprint "eagle-import:R0402")
      (libsource (lib "eagle-import") (part "R-US_R0402"))
    )
    (comp (ref "R47")
      (value "49.9k")
      (footprint "eagle-import:R0402")
      (libsource (lib "eagle-import") (part "R-US_R0402"))
    )
    (comp (ref "R50")
      (value "510")
      (footprint "eagle-import:R0402")
      (libsource (lib "eagle-import") (part "R-US_R0402"))
    )
    (comp (ref "R51")
      (value "49.9k")
      (footprint "eagle-import:R0402")
      (libsource (lib "eagle-import") (part "R-US_R0402"))
    )
    (comp (ref "R53")
      (value "5.1k")
      (footprint "eagle-import:R0402")
      (libsource (lib "eagle-import") (part "R-US_R0402"))
    )
    (comp (ref "R57")
      (value "5.1k")
      (footprint "eagle-import:R0402")
      (libsource (lib "eagle-import") (part "R-US_R0402"))
    )
    (comp (ref "R59")
      (value "5.1k")
      (footprint "eagle-import:R0402")
      (libsource (lib "eagle-import") (part "R-US_R0402"))
    )
    (comp (ref "R64")
      (value "24.9k")
      (footprint "eagle-import:R0402")
      (libsource (lib "eagle-import") (part "R-US_R0402"))
    )
    (comp (ref "R66")
      (value "1.0M")
      (footprint "eagle-import:R0402")
      (libsource (lib "eagle-import") (part "R-US_R0402"))
    )
    (comp (ref "R71")
      (value "1.0M")
      (footprint "eagle-import:R0402")
      (libsource (lib "eagle-import") (part "R-US_R0402"))
    )
    (comp (ref "R74")
      (value "1.0M")
      (footprint "eagle-import:R0402")
      (libsource (lib "eagle-import") (part "R-US_R0402"))
    )
    (comp (ref "R80")
      (value "24.9k")
      (footprint "eagle-import:R0402")
      (libsource (lib "eagle-import") (part "R-US_R0402"))
    )
    (comp (ref "R86")
      (value "1.0M")
      (footprint "eagle-import:R0402")
      (libsource (lib "eagle-import") (part "R-US_R0402"))
    )
    (comp (ref "R87")
      (value "1.0M")
      (footprint "eagle-import:R0402")
      (libsource (lib "eagle-import") (part "R-US_R0402"))
    )
    (comp (ref "R91")
      (value "1.2k")
      (footprint "eagle-import:R0402")
      (libsource (lib "eagle-import") (part "R-US_R0402"))
    )
    (comp (ref "R96")
      (value "510")
      (footprint "eagle-import:R0603")
      (libsource (lib "eagle-import") (part "R-US_R0603"))
    )
    (comp (ref "R101")
      (value "20kB")
      (footprint "eagle-import:BOURNS_SLIDER")
      (libsource (lib "eagle-import") (part "BOURNS_SLIDER"))
    )
    (comp (ref "R104")
      (value "50kB")
      (footprint "eagle-import:ALPS_POT_NARROW")
      (libsource (lib "eagle-import") (part "POT_USVERTICAL_NARROW"))
    )
    (comp (ref "R109")
      (value "10kB")
      (footprint "eagle-import:ALPS_POT_NARROW")
      (libsource (lib "eagle-import") (part "POT_USVERTICAL_NARROW"))
    )
  )
  (nets
    (net (code "1") (name "1_TO_2") (class "Default")
      (node (ref "IC3") (pin "1") (pinfunction "OUT_1") (pintype "output"))
      (node (ref "R23") (pin "1") (pinfunction "1_1") (pintype "passive"))
      (node (ref "R58") (pin "2") (pinfunction "2_2") (pintype "passive"))
    )
    (net (code "2") (name "2_TO_3") (class "Default")
      (node (ref "IC7") (pin "8") (pinfunction "OUT_8") (pintype "output"))
      (node (ref "R30") (pin "2") (pinfunction "2_2") (pintype "passive"))
      (node (ref "R56") (pin "1") (pinfunction "1_1") (pintype "passive"))
    )
    (net (code "3") (name "3_TO_4") (class "Default")
      (node (ref "IC2") (pin "1") (pinfunction "OUT_1") (pintype "output"))
      (node (ref "R22") (pin "1") (pinfunction "1_1") (pintype "passive"))
      (node (ref "R57") (pin "2") (pinfunction "2_2") (pintype "passive"))
    )
    (net (code "4") (name "AREF_+10") (class "Default")
      (node (ref "C42") (pin "1") (pinfunction "1_1") (pintype "passive"))
      (node (ref "IC8") (pin "1") (pinfunction "C_1") (pintype "passive"))
      (node (ref "R102") (pin "P$1") (pinfunction "E_P$1") (pintype "passive"))
      (node (ref "R103") (pin "P$1") (pinfunction "E_P$1") (pintype "passive"))
      (node (ref "R104") (pin "P$1") (pinfunction "E_P$1") (pintype "passive"))
      (node (ref "R105") (pin "P$1") (pinfunction "E_P$1") (pintype "passive"))
      (node (ref "R61") (pin "2") (pinfunction "2_2") (pintype "passive"))
      (node (ref "R62") (pin "2") (pinfunction "2_2") (pintype "passive"))
      (node (ref "R63") (pin "2") (pinfunction "2_2") (pintype "passive"))
      (node (ref "R64") (pin "2") (pinfunction "2_2") (pintype "passive"))
      (node (ref "R69") (pin "2") (pinfunction "2_2") (pintype "passive"))
    )
    (net (code "5") (name "AREF_-2.5") (class "Default")
      (node (ref "C1") (pin "1") (pinfunction "1_1") (pintype "passive"))
      (node (ref "IC1") (pin "2") (pinfunction "A_2") (pintype "passive"))
      (node (ref "R18") (pin "2") (pinfunction "2_2") (pintype "passive"))
      (node (ref "R19") (pin "2") (pinfunction "2_2") (pintype "passive"))
      (node (ref "R20") (pin "2") (pinfunction "2_2") (pintype "passive"))
      (node (ref "R21") (pin "2") (pinfunction "2_2") (pintype "passive"))
      (node (ref "R35") (pin "2") (pinfunction "2_2") (pintype "passive"))
      (node (ref "R36") (pin "2") (pinfunction "2_2") (pintype "passive"))
      (node (ref "R45") (pin "2") (pinfunction "2_2") (pintype "passive"))
      (node (ref "R46") (pin "2") (pinfunction "2_2") (pintype "passive"))
      (node (ref "R5") (pin "2") (pinfunction "2_2") (pintype "passive"))
      (node (ref "R74") (pin "1") (pinfunction "1_1") (pintype "passive"))
      (node (ref "R75") (pin "1") (pinfunction "1_1") (pintype "passive"))
      (node (ref "R76") (pin "1") (pinfunction "1_1") (pintype "passive"))
      (node (ref "R77") (pin "1") (pinfunction "1_1") (pintype "passive"))
    )
    (net (code "6") (name "GND") (class "Default")
      (node (ref "C1") (pin "2") (pinfunction "2_2") (pintype "passive"))
      (node (ref "C10") (pin "2") (pinfunction "2_2") (pintype "passive"))
      (node (ref "C11") (pin "2") (pinfunction "2_2") (pintype "passive"))
      (node (ref "C12") (pin "1") (pinfunction "1_1") (pintype "passive"))
      (node (ref "C13") (pin "1") (pinfunction "1_1") (pintype "passive"))
      (node (ref "C18") (pin "2") (pinfunction "2_2") (pintype "passive"))
      (node (ref "C19") (pin "2") (pinfunction "2_2") (pintype "passive"))
      (node (ref "C2") (pin "2") (pinfunction "2_2") (pintype "passive"))
      (node (ref "C20") (pin "2") (pinfunction "2_2") (pintype "passive"))
      (node (ref "C21") (pin "2") (pinfunction "2_2") (pintype "passive"))
      (node (ref "C22") (pin "2") (pinfunction "2_2") (pintype "passive"))
      (node (ref "C23") (pin "2") (pinfunction "2_2") (pintype "passive"))
      (node (ref "C24") (pin "2") (pinfunction "2_2") (pintype "passive"))
      (node (ref "C25") (pin "2") (pinfunction "2_2") (pintype "passive"))
      (node (ref "C26") (pin "1") (pinfunction "1_1") (pintype "passive"))
      (node (ref "C27") (pin "2") (pinfunction "2_2") (pintype "passive"))
      (node (ref "C28") (pin "2") (pinfunction "2_2") (pintype "passive"))
      (node (ref "C29") (pin "1") (pinfunction "1_1") (pintype "passive"))
      (node (ref "C3") (pin "2") (pinfunction "2_2") (pintype "passive"))
      (node (ref "C34") (pin "2") (pinfunction "2_2") (pintype "passive"))
      (node (ref "C35") (pin "2") (pinfunction "2_2") (pintype "passive"))
      (node (ref "C36") (pin "2") (pinfunction "2_2") (pintype "passive"))
      (node (ref "C37") (pin "2") (pinfunction "2_2") (pintype "passive"))
      (node (ref "C38") (pin "1") (pinfunction "1_1") (pintype "passive"))
      (node (ref "C39") (pin "1") (pinfunction "1_1") (pintype "passive"))
      (node (ref "C4") (pin "2") (pinfunction "2_2") (pintype "passive"))
      (node (ref "C42") (pin "2") (pinfunction "2_2") (pintype "passive"))
      (node (ref "C43") (pin "2") (pinfunction "2_2") (pintype "passive"))
      (node (ref "C44") (pin "1") (pinfunction "1_1") (pintype "passive"))
      (node (ref "C45") (pin "2") (pinfunction "2_2") (pintype "passive"))
      (node (ref "C46") (pin "1") (pinfunction "1_1") (pintype "passive"))
      (node (ref "C47") (pin "1") (pinfunction "1_1") (pintype "passive"))
      (node (ref "C48") (pin "2") (pinfunction "2_2") (pintype "passive"))
      (node (ref "C49") (pin "1") (pinfunction "1_1") (pintype "passive"))
      (node (ref "C5") (pin "2") (pinfunction "2_2") (pintype "passive"))
      (node (ref "C50") (pin "2") (pinfunction "2_2") (pintype "passive"))
      (node (ref "C6") (pin "1") (pinfunction "1_1") (pintype "passive"))
      (node (ref "C7") (pin "1") (pinfunction "1_1") (pintype "passive"))
      (node (ref "D1") (pin "C") (pinfunction "C_C") (pintype "passive"))
      (node (ref "IC1") (pin "1") (pinfunction "C_1") (pintype "passive"))
      (node (ref "IC10") (pin "10") (pinfunction "+IN_10") (pintype "input"))
      (node (ref "IC10") (pin "12") (pinfunction "+IN_12") (pintype "input"))
      (node (ref "IC2") (pin "10") (pinfunction "+IN_10") (pintype "input"))
      (node (ref "IC2") (pin "12") (pinfunction "+IN_12") (pintype "input"))
      (node (ref "IC2") (pin "3") (pinfunction "+IN_3") (pintype "input"))
      (node (ref "IC2") (pin "5") (pinfunction "+IN_5") (pintype "input"))
      (node (ref "IC3") (pin "10") (pinfunction "+IN_10") (pintype "input"))
      (node (ref "IC3") (pin "12") (pinfunction "+IN_12") (pintype "input"))
      (node (ref "IC3") (pin "3") (pinfunction "+IN_3") (pintype "input"))
      (node (ref "IC3") (pin "5") (pinfunction "+IN_5") (pintype "input"))
      (node (ref "IC4") (pin "8") (pinfunction "GND_8") (pintype "power_in"))
      (node (ref "IC5") (pin "8") (pinfunction "GND_8") (pintype "power_in"))
      (node (ref "IC6") (pin "10") (pinfunction "+IN_10") (pintype "input"))
      (node (ref "IC6") (pin "12") (pinfunction "+IN_12") (pintype "input"))
      (node (ref "IC6") (pin "3") (pinfunction "+IN_3") (pintype "input"))
      (node (ref "IC6") (pin "5") (pinfunction "+IN_5") (pintype "input"))
      (node (ref "IC7") (pin "10") (pinfunction "+IN_10") (pintype "input"))
      (node (ref "IC7") (pin "12") (pinfunction "+IN_12") (pintype "input"))
      (node (ref "IC7") (pin "3") (pinfunction "+IN_3") (pintype "input"))
      (node (ref "IC7") (pin "5") (pinfunction "+IN_5") (pintype "input"))
      (node (ref "IC8") (pin "2") (pinfunction "A_2") (pintype "passive"))
      (node (ref "IC9") (pin "10") (pinfunction "+IN_10") (pintype "input"))
      (node (ref "IC9") (pin "12") (pinfunction "+IN_12") (pintype "input"))
      (node (ref "J1") (pin "P1") (pinfunction "1_P1") (pintype "passive"))
      (node (ref "J10") (pin "P1") (pinfunction "1_P1") (pintype "passive"))
      (node (ref "J11") (pin "P1") (pinfunction "1_P1") (pintype "passive"))
      (node (ref "J12") (pin "P1") (pinfunction "1_P1") (pintype "passive"))
      (node (ref "J2") (pin "P1") (pinfunction "1_P1") (pintype "passive"))
      (node (ref "J3") (pin "P1") (pinfunction "1_P1") (pintype "passive"))
      (node (ref "J4") (pin "P1") (pinfunction "1_P1") (pintype "passive"))
      (node (ref "J5") (pin "P1") (pinfunction "1_P1") (pintype "passive"))
      (node (ref "J5") (pin "P2") (pinfunction "2_P2") (pintype "passive"))
      (node (ref "J6") (pin "P1") (pinfunction "1_P1") (pintype "passive"))
      (node (ref "J6") (pin "P2") (pinfunction "2_P2") (pintype "passive"))
      (node (ref "J7") (pin "P1") (pinfunction "1_P1") (pintype "passive"))
      (node (ref "J7") (pin "P2") (pinfunction "2_P2") (pintype "passive"))
      (node (ref "J8") (pin "P1") (pinfunction "1_P1") (pintype "passive"))
      (node (ref "J8") (pin "P2") (pinfunction "2_P2") (pintype "passive"))
      (node (ref "J9") (pin "P1") (pinfunction "1_P1") (pintype "passive"))
      (node (ref "JP1") (pin "3") (pinfunction "3_3") (pintype "passive"))
      (node (ref "JP1") (pin "4") (pinfunction "4_4") (pintype "passive"))
      (node (ref "JP1") (pin "5") (pinfunction "5_5") (pintype "passive"))
      (node (ref "JP1") (pin "6") (pinfunction "6_6") (pintype "passive"))
      (node (ref "JP1") (pin "7") (pinfunction "7_7") (pintype "passive"))
      (node (ref "JP1") (pin "8") (pinfunction "8_8") (pintype "passive"))
      (node (ref "R1") (pin "1") (pinfunction "1_1") (pintype "passive"))
      (node (ref "R10") (pin "2") (pinfunction "2_2") (pintype "passive"))
      (node (ref "R100") (pin "3") (pinfunction "E_3") (pintype "passive"))
      (node (ref "R101") (pin "3") (pinfunction "E_3") (pintype "passive"))
      (node (ref "R102") (pin "P$3") (pinfunction "A_P$3") (pintype "passive"))
      (node (ref "R103") (pin "P$3") (pinfunction "A_P$3") (pintype "passive"))
      (node (ref "R104") (pin "P$3") (pinfunction "A_P$3") (pintype "passive"))
      (node (ref "R105") (pin "P$3") (pinfunction "A_P$3") (pintype "passive"))
      (node (ref "R11") (pin "2") (pinfunction "2_2") (pintype "passive"))
      (node (ref "R12") (pin "2") (pinfunction "2_2") (pintype "passive"))
      (node (ref "R13") (pin "2") (pinfunction "2_2") (pintype "passive"))
      (node (ref "R2") (pin "1") (pinfunction "1_1") (pintype "passive"))
      (node (ref "R3") (pin "1") (pinfunction "1_1") (pintype "passive"))
      (node (ref "R4") (pin "1") (pinfunction "1_1") (pintype "passive"))
      (node (ref "R83") (pin "1") (pinfunction "1_1") (pintype "passive"))
      (node (ref "R84") (pin "1") (pinfunction "1_1") (pintype "passive"))
      (node (ref "R87") (pin "1") (pinfunction "1_1") (pintype "passive"))
      (node (ref "R88") (pin "1") (pinfunction "1_1") (pintype "passive"))
      (node (ref "R90") (pin "2") (pinfunction "2_2") (pintype "passive"))
      (node (ref "R91") (pin "2") (pinfunction "2_2") (pintype "passive"))
      (node (ref "R92") (pin "2") (pinfunction "2_2") (pintype "passive"))
      (node (ref "R93") (pin "2") (pinfunction "2_2") (pintype "passive"))
      (node (ref "R98") (pin "3") (pinfunction "E_3") (pintype "passive"))
      (node (ref "R99") (pin "3") (pinfunction "E_3") (pintype "passive"))
    )
    (net (code "7") (name "Net-(C20-Pad1)") (class "Default")
      (node (ref "C20") (pin "1") (pinfunction "1_1") (pintype "passive"))
      (node (ref "R39") (pin "1") (pinfunction "1_1") (pintype "passive"))
    )
    (net (code "8") (name "Net-(C21-Pad1)") (class "Default")
      (node (ref "C21") (pin "1") (pinfunction "1_1") (pintype "passive"))
      (node (ref "R40") (pin "1") (pinfunction "1_1") (pintype "passive"))
    )
    (net (code "9") (name "Net-(C22-Pad1)") (class "Default")
      (node (ref "C22") (pin "1") (pinfunction "1_1") (pintype "passive"))
      (node (ref "R41") (pin "1") (pinfunction "1_1") (pintype "passive"))
    )
    (net (code "10") (name "Net-(C23-Pad1)") (class "Default")
      (node (ref "C23") (pin "1") (pinfunction "1_1") (pintype "passive"))
      (node (ref "R42") (pin "1") (pinfunction "1_1") (pintype "passive"))
    )
    (net (code "11") (name "Net-(C24-Pad1)") (class "Default")
      (node (ref "C24") (pin "1") (pinfunction "1_1") (pintype "passive"))
      (node (ref "R43") (pin "1") (pinfunction "1_1") (pintype "passive"))
    )
    (net (code "12") (name "Net-(C25-Pad1)") (class "Default")
      (node (ref "C25") (pin "1") (pinfunction "1_1") (pintype "passive"))
      (node (ref "R44") (pin "1") (pinfunction "1_1") (pintype "passive"))
    )
    (net (code "13") (name "Net-(C27-Pad1)") (class "Default")
      (node (ref "C27") (pin "1") (pinfunction "1_1") (pintype "passive"))
      (node (ref "R49") (pin "1") (pinfunction "1_1") (pintype "passive"))
    )
    (net (code "14") (name "Net-(C28-Pad1)") (class "Default")
      (node (ref "C28") (pin "1") (pinfunction "1_1") (pintype "passive"))
      (node (ref "R50") (pin "1") (pinfunction "1_1") (pintype "passive"))
    )
    (net (code "15") (name "Net-(D2-PadA)") (class "Default")
      (node (ref "D2") (pin "A") (pinfunction "A_A") (pintype "passive"))
      (node (ref "JP1") (pin "1") (pinfunction "1_1") (pintype "passive"))
      (node (ref "JP1") (pin "2") (pinfunction "2_2") (pintype "passive"))
    )
    (net (code "16") (name "Net-(D2-PadC)") (class "Default")
      (node (ref "D2") (pin "C") (pinfunction "C_C") (pintype "passive"))
      (node (ref "L2") (pin "2") (pinfunction "2_2") (pintype "passive"))
    )
    (net (code "17") (name "Net-(IC2A--IN)") (class "Default")
      (node (ref "IC2") (pin "2") (pinfunction "-IN_2") (pintype "input"))
      (node (ref "R22") (pin "2") (pinfunction "2_2") (pintype "passive"))
      (node (ref "R24") (pin "1") (pinfunction "1_1") (pintype "passive"))
    )
    (net (code "18") (name "Net-(IC2B--IN)") (class "Default")
      (node (ref "C16") (pin "1") (pinfunction "1_1") (pintype "passive"))
      (node (ref "IC2") (pin "6") (pinfunction "-IN_6") (pintype "input"))
      (node (ref "IC4") (pin "13") (pinfunction "OUT_13") (pintype "output"))
      (node (ref "R31") (pin "2") (pinfunction "2_2") (pintype "passive"))
    )
    (net (code "19") (name "Net-(IC2B-OUT)") (class "Default")
      (node (ref "C16") (pin "2") (pinfunction "2_2") (pintype "passive"))
      (node (ref "IC2") (pin "7") (pinfunction "OUT_7") (pintype "output"))
      (node (ref "R26") (pin "2") (pinfunction "2_2") (pintype "passive"))
      (node (ref "R31") (pin "1") (pinfunction "1_1") (pintype "passive"))
    )
    (net (code "20") (name "Net-(IC2C--IN)") (class "Default")
      (node (ref "C14") (pin "1") (pinfunction "1_1") (pintype "passive"))
      (node (ref "IC2") (pin "9") (pinfunction "-IN_9") (pintype "input"))
      (node (ref "R26") (pin "1") (pinfunction "1_1") (pintype "passive"))
      (node (ref "R28") (pin "2") (pinfunction "2_2") (pintype "passive"))
      (node (ref "R30") (pin "1") (pinfunction "1_1") (pintype "passive"))
    )
    (net (code "21") (name "Net-(IC2C-OUT)") (class "Default")
      (node (ref "C14") (pin "2") (pinfunction "2_2") (pintype "passive"))
      (node (ref "IC2") (pin "8") (pinfunction "OUT_8") (pintype "output"))
      (node (ref "R28") (pin "1") (pinfunction "1_1") (pintype "passive"))
      (node (ref "R89") (pin "1") (pinfunction "1_1") (pintype "passive"))
      (node (ref "R94") (pin "2") (pinfunction "2_2") (pintype "passive"))
    )
    (net (code "22") (name "Net-(IC2D--IN)") (class "Default")
      (node (ref "C8") (pin "1") (pinfunction "1_1") (pintype "passive"))
      (node (ref "IC2") (pin "13") (pinfunction "-IN_13") (pintype "input"))
      (node (ref "IC4") (pin "4") (pinfunction "OUT_4") (pintype "output"))
      (node (ref "R100") (pin "1") (pinfunction "A_1") (pintype "passive"))
      (node (ref "R16") (pin "1") (pinfunction "1_1") (pintype "passive"))
      (node (ref "R19") (pin "1") (pinfunction "1_1") (pintype "passive"))
    )
    (net (code "23") (name "Net-(IC2D-OUT)") (class "Default")
      (node (ref "C8") (pin "2") (pinfunction "2_2") (pintype "passive"))
      (node (ref "IC2") (pin "14") (pinfunction "OUT_14") (pintype "output"))
      (node (ref "IC4") (pin "14") (pinfunction "CTRL_14") (pintype "input"))
      (node (ref "R108") (pin "P$1") (pinfunction "E_P$1") (pintype "passive"))
      (node (ref "R65") (pin "1") (pinfunction "1_1") (pintype "passive"))
    )
    (net (code "24") (name "Net-(IC3A--IN)") (class "Default")
      (node (ref "IC3") (pin "2") (pinfunction "-IN_2") (pintype "input"))
      (node (ref "R23") (pin "2") (pinfunction "2_2") (pintype "passive"))
      (node (ref "R25") (pin "1") (pinfunction "1_1") (pintype "passive"))
    )
    (net (code "25") (name "Net-(IC3B--IN)") (class "Default")
      (node (ref "C17") (pin "1") (pinfunction "1_1") (pintype "passive"))
      (node (ref "IC3") (pin "6") (pinfunction "-IN_6") (pintype "input"))
      (node (ref "IC5") (pin "13") (pinfunction "OUT_13") (pintype "output"))
      (node (ref "R32") (pin "2") (pinfunction "2_2") (pintype "passive"))
    )
    (net (code "26") (name "Net-(IC3B-OUT)") (class "Default")
      (node (ref "C17") (pin "2") (pinfunction "2_2") (pintype "passive"))
      (node (ref "IC3") (pin "7") (pinfunction "OUT_7") (pintype "output"))
      (node (ref "R27") (pin "2") (pinfunction "2_2") (pintype "passive"))
      (node (ref "R32") (pin "1") (pinfunction "1_1") (pintype "passive"))
    )
    (net (code "27") (name "Net-(IC3C--IN)") (class "Default")
      (node (ref "C15") (pin "1") (pinfunction "1_1") (pintype "passive"))
      (node (ref "IC3") (pin "9") (pinfunction "-IN_9") (pintype "input"))
      (node (ref "R27") (pin "1") (pinfunction "1_1") (pintype "passive"))
      (node (ref "R29") (pin "2") (pinfunction "2_2") (pintype "passive"))
    )
    (net (code "28") (name "Net-(IC3C-OUT)") (class "Default")
      (node (ref "C15") (pin "2") (pinfunction "2_2") (pintype "passive"))
      (node (ref "IC3") (pin "8") (pinfunction "OUT_8") (pintype "output"))
      (node (ref "R29") (pin "1") (pinfunction "1_1") (pintype "passive"))
      (node (ref "R85") (pin "1") (pinfunction "1_1") (pintype "passive"))
      (node (ref "R95") (pin "2") (pinfunction "2_2") (pintype "passive"))
    )
    (net (code "29") (name "Net-(IC3D--IN)") (class "Default")
      (node (ref "C9") (pin "1") (pinfunction "1_1") (pintype "passive"))
      (node (ref "IC3") (pin "13") (pinfunction "-IN_13") (pintype "input"))
      (node (ref "IC5") (pin "4") (pinfunction "OUT_4") (pintype "output"))
      (node (ref "R15") (pin "1") (pinfunction "1_1") (pintype "passive"))
      (node (ref "R21") (pin "1") (pinfunction "1_1") (pintype "passive"))
      (node (ref "R98") (pin "1") (pinfunction "A_1") (pintype "passive"))
    )
    (net (code "30") (name "Net-(IC3D-OUT)") (class "Default")
      (node (ref "C9") (pin "2") (pinfunction "2_2") (pintype "passive"))
      (node (ref "IC3") (pin "14") (pinfunction "OUT_14") (pintype "output"))
      (node (ref "IC5") (pin "14") (pinfunction "CTRL_14") (pintype "input"))
      (node (ref "R106") (pin "P$1") (pinfunction "E_P$1") (pintype "passive"))
      (node (ref "R68") (pin "1") (pinfunction "1_1") (pintype "passive"))
    )
    (net (code "31") (name "Net-(IC4A-CTRL)") (class "Default")
      (node (ref "IC4") (pin "3") (pinfunction "CTRL_3") (pintype "input"))
      (node (ref "R108") (pin "P$2") (pinfunction "S_P$2") (pintype "passive"))
    )
    (net (code "32") (name "Net-(IC4A-IN)") (class "Default")
      (node (ref "IC4") (pin "2") (pinfunction "IN_2") (pintype "input"))
      (node (ref "R35") (pin "1") (pinfunction "1_1") (pintype "passive"))
      (node (ref "R39") (pin "2") (pinfunction "2_2") (pintype "passive"))
    )
    (net (code "33") (name "Net-(IC4B-CTRL)") (class "Default")
      (node (ref "IC4") (pin "6") (pinfunction "CTRL_6") (pintype "input"))
      (node (ref "R109") (pin "P$2") (pinfunction "S_P$2") (pintype "passive"))
    )
    (net (code "34") (name "Net-(IC4B-IN)") (class "Default")
      (node (ref "IC4") (pin "7") (pinfunction "IN_7") (pintype "input"))
      (node (ref "R46") (pin "1") (pinfunction "1_1") (pintype "passive"))
      (node (ref "R50") (pin "2") (pinfunction "2_2") (pintype "passive"))
    )
    (net (code "35") (name "Net-(IC4B-OUT)") (class "Default")
      (node (ref "C30") (pin "1") (pinfunction "1_1") (pintype "passive"))
      (node (ref "IC4") (pin "5") (pinfunction "OUT_5") (pintype "output"))
      (node (ref "IC6") (pin "2") (pinfunction "-IN_2") (pintype "input"))
      (node (ref "R101") (pin "1") (pinfunction "A_1") (pintype "passive"))
      (node (ref "R17") (pin "1") (pinfunction "1_1") (pintype "passive"))
      (node (ref "R18") (pin "1") (pinfunction "1_1") (pintype "passive"))
    )
    (net (code "36") (name "Net-(IC4C-CTRL)") (class "Default")
      (node (ref "C30") (pin "2") (pinfunction "2_2") (pintype "passive"))
      (node (ref "IC4") (pin "11") (pinfunction "CTRL_11") (pintype "input"))
      (node (ref "IC6") (pin "1") (pinfunction "OUT_1") (pintype "output"))
      (node (ref "R109") (pin "P$1") (pinfunction "E_P$1") (pintype "passive"))
      (node (ref "R66") (pin "1") (pinfunction "1_1") (pintype "passive"))
    )
    (net (code "37") (name "Net-(IC4C-IN)") (class "Default")
      (node (ref "IC4") (pin "10") (pinfunction "IN_10") (pintype "input"))
      (node (ref "R43") (pin "2") (pinfunction "2_2") (pintype "passive"))
      (node (ref "R47") (pin "1") (pinfunction "1_1") (pintype "passive"))
    )
    (net (code "38") (name "Net-(IC4C-OUT)") (class "Default")
      (node (ref "C32") (pin "1") (pinfunction "1_1") (pintype "passive"))
      (node (ref "IC4") (pin "12") (pinfunction "OUT_12") (pintype "output"))
      (node (ref "IC6") (pin "13") (pinfunction "-IN_13") (pintype "input"))
      (node (ref "R51") (pin "2") (pinfunction "2_2") (pintype "passive"))
    )
    (net (code "39") (name "Net-(IC4D-IN)") (class "Default")
      (node (ref "IC4") (pin "15") (pinfunction "IN_15") (pintype "input"))
      (node (ref "R37") (pin "1") (pinfunction "1_1") (pintype "passive"))
      (node (ref "R41") (pin "2") (pinfunction "2_2") (pintype "passive"))
    )
    (net (code "40") (name "Net-(IC4E-MODE)") (class "Default")
      (node (ref "IC4") (pin "1") (pinfunction "MODE_1") (pintype "input"))
      (node (ref "R34") (pin "2") (pinfunction "2_2") (pintype "passive"))
    )
    (net (code "41") (name "Net-(IC5A-CTRL)") (class "Default")
      (node (ref "IC5") (pin "3") (pinfunction "CTRL_3") (pintype "input"))
      (node (ref "R106") (pin "P$2") (pinfunction "S_P$2") (pintype "passive"))
    )
    (net (code "42") (name "Net-(IC5A-IN)") (class "Default")
      (node (ref "IC5") (pin "2") (pinfunction "IN_2") (pintype "input"))
      (node (ref "R36") (pin "1") (pinfunction "1_1") (pintype "passive"))
      (node (ref "R40") (pin "2") (pinfunction "2_2") (pintype "passive"))
    )
    (net (code "43") (name "Net-(IC5B-CTRL)") (class "Default")
      (node (ref "IC5") (pin "6") (pinfunction "CTRL_6") (pintype "input"))
      (node (ref "R107") (pin "P$2") (pinfunction "S_P$2") (pintype "passive"))
    )
    (net (code "44") (name "Net-(IC5B-IN)") (class "Default")
      (node (ref "IC5") (pin "7") (pinfunction "IN_7") (pintype "input"))
      (node (ref "R45") (pin "1") (pinfunction "1_1") (pintype "passive"))
      (node (ref "R49") (pin "2") (pinfunction "2_2") (pintype "passive"))
    )
    (net (code "45") (name "Net-(IC5B-OUT)") (class "Default")
      (node (ref "C33") (pin "1") (pinfunction "1_1") (pintype "passive"))
      (node (ref "IC5") (pin "5") (pinfunction "OUT_5") (pintype "output"))
      (node (ref "IC7") (pin "2") (pinfunction "-IN_2") (pintype "input"))
      (node (ref "R14") (pin "1") (pinfunction "1_1") (pintype "passive"))
      (node (ref "R20") (pin "1") (pinfunction "1_1") (pintype "passive"))
      (node (ref "R99") (pin "1") (pinfunction "A_1") (pintype "passive"))
    )
    (net (code "46") (name "Net-(IC5C-CTRL)") (class "Default")
      (node (ref "C33") (pin "2") (pinfunction "2_2") (pintype "passive"))
      (node (ref "IC5") (pin "11") (pinfunction "CTRL_11") (pintype "input"))
      (node (ref "IC7") (pin "1") (pinfunction "OUT_1") (pintype "output"))
      (node (ref "R107") (pin "P$1") (pinfunction "E_P$1") (pintype "passive"))
      (node (ref "R67") (pin "1") (pinfunction "1_1") (pintype "passive"))
    )
    (net (code "47") (name "Net-(IC5C-IN)") (class "Default")
      (node (ref "IC5") (pin "10") (pinfunction "IN_10") (pintype "input"))
      (node (ref "R44") (pin "2") (pinfunction "2_2") (pintype "passive"))
      (node (ref "R48") (pin "1") (pinfunction "1_1") (pintype "passive"))
    )
    (net (code "48") (name "Net-(IC5C-OUT)") (class "Default")
      (node (ref "C31") (pin "1") (pinfunction "1_1") (pintype "passive"))
      (node (ref "IC5") (pin "12") (pinfunction "OUT_12") (pintype "output"))
      (node (ref "IC7") (pin "13") (pinfunction "-IN_13") (pintype "input"))
      (node (ref "R52") (pin "2") (pinfunction "2_2") (pintype "passive"))
    )
    (net (code "49") (name "Net-(IC5D-IN)") (class "Default")
      (node (ref "IC5") (pin "15") (pinfunction "IN_15") (pintype "input"))
      (node (ref "R38") (pin "1") (pinfunction "1_1") (pintype "passive"))
      (node (ref "R42") (pin "2") (pinfunction "2_2") (pintype "passive"))
    )
    (net (code "50") (name "Net-(IC5E-MODE)") (class "Default")
      (node (ref "IC5") (pin "1") (pinfunction "MODE_1") (pintype "input"))
      (node (ref "R33") (pin "2") (pinfunction "2_2") (pintype "passive"))
    )
    (net (code "51") (name "Net-(IC6B--IN)") (class "Default")
      (node (ref "C41") (pin "1") (pinfunction "1_1") (pintype "passive"))
      (node (ref "IC6") (pin "6") (pinfunction "-IN_6") (pintype "input"))
      (node (ref "R53") (pin "1") (pinfunction "1_1") (pintype "passive"))
      (node (ref "R57") (pin "1") (pinfunction "1_1") (pintype "passive"))
      (node (ref "R59") (pin "2") (pinfunction "2_2") (pintype "passive"))
    )
    (net (code "52") (name "Net-(IC6B-OUT)") (class "Default")
      (node (ref "C41") (pin "2") (pinfunction "2_2") (pintype "passive"))
      (node (ref "IC6") (pin "7") (pinfunction "OUT_7") (pintype "output"))
      (node (ref "R59") (pin "1") (pinfunction "1_1") (pintype "passive"))
      (node (ref "R86") (pin "1") (pinfunction "1_1") (pintype "passive"))
      (node (ref "R96") (pin "2") (pinfunction "2_2") (pintype "passive"))
    )
    (net (code "53") (name "Net-(IC6C--IN)") (class "Default")
      (node (ref "IC6") (pin "8") (pinfunction "OUT_8") (pintype "output"))
      (node (ref "IC6") (pin "9") (pinfunction "-IN_9") (pintype "input"))
    )
    (net (code "54") (name "Net-(IC6D-OUT)") (class "Default")
      (node (ref "C32") (pin "2") (pinfunction "2_2") (pintype "passive"))
      (node (ref "IC6") (pin "14") (pinfunction "OUT_14") (pintype "output"))
      (node (ref "R51") (pin "1") (pinfunction "1_1") (pintype "passive"))
      (node (ref "R53") (pin "2") (pinfunction "2_2") (pintype "passive"))
    )
    (net (code "55") (name "Net-(IC7B--IN)") (class "Default")
      (node (ref "C40") (pin "1") (pinfunction "1_1") (pintype "passive"))
      (node (ref "IC7") (pin "6") (pinfunction "-IN_6") (pintype "input"))
      (node (ref "R54") (pin "1") (pinfunction "1_1") (pintype "passive"))
      (node (ref "R58") (pin "1") (pinfunction "1_1") (pintype "passive"))
      (node (ref "R60") (pin "2") (pinfunction "2_2") (pintype "passive"))
    )
    (net (code "56") (name "Net-(IC7B-OUT)") (class "Default")
      (node (ref "C40") (pin "2") (pinfunction "2_2") (pintype "passive"))
      (node (ref "IC7") (pin "7") (pinfunction "OUT_7") (pintype "output"))
      (node (ref "R60") (pin "1") (pinfunction "1_1") (pintype "passive"))
      (node (ref "R82") (pin "1") (pinfunction "1_1") (pintype "passive"))
      (node (ref "R97") (pin "2") (pinfunction "2_2") (pintype "passive"))
    )
    (net (code "57") (name "Net-(IC7C--IN)") (class "Default")
      (node (ref "IC7") (pin "9") (pinfunction "-IN_9") (pintype "input"))
      (node (ref "R55") (pin "1") (pinfunction "1_1") (pintype "passive"))
      (node (ref "R56") (pin "2") (pinfunction "2_2") (pintype "passive"))
    )
    (net (code "58") (name "Net-(IC7D-OUT)") (class "Default")
      (node (ref "C31") (pin "2") (pinfunction "2_2") (pintype "passive"))
      (node (ref "IC7") (pin "14") (pinfunction "OUT_14") (pintype "output"))
      (node (ref "R52") (pin "1") (pinfunction "1_1") (pintype "passive"))
      (node (ref "R54") (pin "2") (pinfunction "2_2") (pintype "passive"))
    )
    (net (code "59") (name "Net-(IC9A-+IN)") (class "Default")
      (node (ref "IC9") (pin "3") (pinfunction "+IN_3") (pintype "input"))
      (node (ref "R86") (pin "2") (pinfunction "2_2") (pintype "passive"))
      (node (ref "R87") (pin "2") (pinfunction "2_2") (pintype "passive"))
    )
    (net (code "60") (name "Net-(IC9A--IN)") (class "Default")
      (node (ref "IC9") (pin "2") (pinfunction "-IN_2") (pintype "input"))
      (node (ref "LED4") (pin "A") (pinfunction "A_A") (pintype "passive"))
      (node (ref "R91") (pin "1") (pinfunction "1_1") (pintype "passive"))
    )
    (net (code "61") (name "Net-(IC9A-OUT)") (class "Default")
      (node (ref "IC9") (pin "1") (pinfunction "OUT_1") (pintype "output"))
      (node (ref "LED4") (pin "K") (pinfunction "C_K") (pintype "passive"))
    )
    (net (code "62") (name "Net-(IC9B-+IN)") (class "Default")
      (node (ref "IC9") (pin "5") (pinfunction "+IN_5") (pintype "input"))
      (node (ref "R88") (pin "2") (pinfunction "2_2") (pintype "passive"))
      (node (ref "R89") (pin "2") (pinfunction "2_2") (pintype "passive"))
    )
    (net (code "63") (name "Net-(IC9B--IN)") (class "Default")
      (node (ref "IC9") (pin "6") (pinfunction "-IN_6") (pintype "input"))
      (node (ref "LED3") (pin "A") (pinfunction "A_A") (pintype "passive"))
      (node (ref "R92") (pin "1") (pinfunction "1_1") (pintype "passive"))
    )
    (net (code "64") (name "Net-(IC9B-OUT)") (class "Default")
      (node (ref "IC9") (pin "7") (pinfunction "OUT_7") (pintype "output"))
      (node (ref "LED3") (pin "K") (pinfunction "C_K") (pintype "passive"))
    )
    (net (code "65") (name "Net-(IC9C--IN)") (class "Default")
      (node (ref "IC9") (pin "9") (pinfunction "-IN_9") (pintype "input"))
      (node (ref "R65") (pin "2") (pinfunction "2_2") (pintype "passive"))
      (node (ref "R70") (pin "1") (pinfunction "1_1") (pintype "passive"))
      (node (ref "R75") (pin "2") (pinfunction "2_2") (pintype "passive"))
    )
    (net (code "66") (name "Net-(IC9C-OUT)") (class "Default")
      (node (ref "IC9") (pin "8") (pinfunction "OUT_8") (pintype "output"))
      (node (ref "R78") (pin "1") (pinfunction "1_1") (pintype "passive"))
    )
    (net (code "67") (name "Net-(IC9D--IN)") (class "Default")
      (node (ref "IC9") (pin "13") (pinfunction "-IN_13") (pintype "input"))
      (node (ref "R66") (pin "2") (pinfunction "2_2") (pintype "passive"))
      (node (ref "R71") (pin "1") (pinfunction "1_1") (pintype "passive"))
      (node (ref "R74") (pin "2") (pinfunction "2_2") (pintype "passive"))
    )
    (net (code "68") (name "Net-(IC9D-OUT)") (class "Default")
      (node (ref "IC9") (pin "14") (pinfunction "OUT_14") (pintype "output"))
      (node (ref "R80") (pin "1") (pinfunction "1_1") (pintype "passive"))
    )
    (net (code "69") (name "Net-(IC10A-+IN)") (class "Default")
      (node (ref "IC10") (pin "3") (pinfunction "+IN_3") (pintype "input"))
      (node (ref "R82") (pin "2") (pinfunction "2_2") (pintype "passive"))
      (node (ref "R83") (pin "2") (pinfunction "2_2") (pintype "passive"))
    )
    (net (code "70") (name "Net-(IC10A--IN)") (class "Default")
      (node (ref "IC10") (pin "2") (pinfunction "-IN_2") (pintype "input"))
      (node (ref "LED2") (pin "A") (pinfunction "A_A") (pintype "passive"))
      (node (ref "R93") (pin "1") (pinfunction "1_1") (pintype "passive"))
    )
    (net (code "71") (name "Net-(IC10A-OUT)") (class "Default")
      (node (ref "IC10") (pin "1") (pinfunction "OUT_1") (pintype "output"))
      (node (ref "LED2") (pin "K") (pinfunction "C_K") (pintype "passive"))
    )
    (net (code "72") (name "Net-(IC10B-+IN)") (class "Default")
      (node (ref "IC10") (pin "5") (pinfunction "+IN_5") (pintype "input"))
      (node (ref "R84") (pin "2") (pinfunction "2_2") (pintype "passive"))
      (node (ref "R85") (pin "2") (pinfunction "2_2") (pintype "passive"))
    )
    (net (code "73") (name "Net-(IC10B--IN)") (class "Default")
      (node (ref "IC10") (pin "6") (pinfunction "-IN_6") (pintype "input"))
      (node (ref "LED1") (pin "A") (pinfunction "A_A") (pintype "passive"))
      (node (ref "R90") (pin "1") (pinfunction "1_1") (pintype "passive"))
    )
    (net (code "74") (name "Net-(IC10B-OUT)") (class "Default")
      (node (ref "IC10") (pin "7") (pinfunction "OUT_7") (pintype "output"))
      (node (ref "LED1") (pin "K") (pinfunction "C_K") (pintype "passive"))
    )
    (net (code "75") (name "Net-(IC10C--IN)") (class "Default")
      (node (ref "IC10") (pin "9") (pinfunction "-IN_9") (pintype "input"))
      (node (ref "R68") (pin "2") (pinfunction "2_2") (pintype "passive"))
      (node (ref "R73") (pin "1") (pinfunction "1_1") (pintype "passive"))
      (node (ref "R77") (pin "2") (pinfunction "2_2") (pintype "passive"))
    )
    (net (code "76") (name "Net-(IC10C-OUT)") (class "Default")
      (node (ref "IC10") (pin "8") (pinfunction "OUT_8") (pintype "output"))
      (node (ref "R81") (pin "1") (pinfunction "1_1") (pintype "passive"))
    )
    (net (code "77") (name "Net-(IC10D--IN)") (class "Default")
      (node (ref "IC10") (pin "13") (pinfunction "-IN_13") (pintype "input"))
      (node (ref "R67") (pin "2") (pinfunction "2_2") (pintype "passive"))
      (node (ref "R72") (pin "1") (pinfunction "1_1") (pintype "passive"))
      (node (ref "R76") (pin "2") (pinfunction "2_2") (pintype "passive"))
    )
    (net (code "78") (name "Net-(IC10D-OUT)") (class "Default")
      (node (ref "IC10") (pin "14") (pinfunction "OUT_14") (pintype "output"))
      (node (ref "R79") (pin "1") (pinfunction "1_1") (pintype "passive"))
    )
    (net (code "79") (name "Net-(J1-2)") (class "Default")
      (node (ref "J1") (pin "P2") (pinfunction "2_P2") (pintype "passive"))
      (node (ref "R25") (pin "2") (pinfunction "2_2") (pintype "passive"))
    )
    (net (code "80") (name "Net-(J1-3)") (class "Default")
      (node (ref "J1") (pin "P3") (pinfunction "3_P3") (pintype "passive"))
      (node (ref "R95") (pin "1") (pinfunction "1_1") (pintype "passive"))
    )
    (net (code "81") (name "Net-(J2-2)") (class "Default")
      (node (ref "J2") (pin "P2") (pinfunction "2_P2") (pintype "passive"))
      (node (ref "R55") (pin "2") (pinfunction "2_2") (pintype "passive"))
    )
    (net (code "82") (name "Net-(J2-3)") (class "Default")
      (node (ref "J2") (pin "P3") (pinfunction "3_P3") (pintype "passive"))
      (node (ref "R97") (pin "1") (pinfunction "1_1") (pintype "passive"))
    )
    (net (code "83") (name "Net-(J3-2)") (class "Default")
      (node (ref "J3") (pin "P2") (pinfunction "2_P2") (pintype "passive"))
      (node (ref "R24") (pin "2") (pinfunction "2_2") (pintype "passive"))
    )
    (net (code "84") (name "Net-(J3-3)") (class "Default")
      (node (ref "J3") (pin "P3") (pinfunction "3_P3") (pintype "passive"))
      (node (ref "R94") (pin "1") (pinfunction "1_1") (pintype "passive"))
    )
    (net (code "85") (name "Net-(J4-3)") (class "Default")
      (node (ref "J4") (pin "P3") (pinfunction "3_P3") (pintype "passive"))
      (node (ref "R96") (pin "1") (pinfunction "1_1") (pintype "passive"))
    )
    (net (code "86") (name "Net-(J5-3)") (class "Default")
      (node (ref "J5") (pin "P3") (pinfunction "3_P3") (pintype "passive"))
      (node (ref "R38") (pin "2") (pinfunction "2_2") (pintype "passive"))
    )
    (net (code "87") (name "Net-(J6-3)") (class "Default")
      (node (ref "J6") (pin "P3") (pinfunction "3_P3") (pintype "passive"))
      (node (ref "R48") (pin "2") (pinfunction "2_2") (pintype "passive"))
    )
    (net (code "88") (name "Net-(J7-3)") (class "Default")
      (node (ref "J7") (pin "P3") (pinfunction "3_P3") (pintype "passive"))
      (node (ref "R37") (pin "2") (pinfunction "2_2") (pintype "passive"))
    )
    (net (code "89") (name "Net-(J8-3)") (class "Default")
      (node (ref "J8") (pin "P3") (pinfunction "3_P3") (pintype "passive"))
      (node (ref "R47") (pin "2") (pinfunction "2_2") (pintype "passive"))
    )
    (net (code "90") (name "Net-(J9-2)") (class "Default")
      (node (ref "J9") (pin "P2") (pinfunction "2_P2") (pintype "passive"))
      (node (ref "R61") (pin "1") (pinfunction "1_1") (pintype "passive"))
    )
    (net (code "91") (name "Net-(J9-3)") (class "Default")
      (node (ref "J9") (pin "P3") (pinfunction "3_P3") (pintype "passive"))
      (node (ref "R7") (pin "2") (pinfunction "2_2") (pintype "passive"))
    )
    (net (code "92") (name "Net-(J10-2)") (class "Default")
      (node (ref "J10") (pin "P2") (pinfunction "2_P2") (pintype "passive"))
      (node (ref "R63") (pin "1") (pinfunction "1_1") (pintype "passive"))
    )
    (net (code "93") (name "Net-(J10-3)") (class "Default")
      (node (ref "J10") (pin "P3") (pinfunction "3_P3") (pintype "passive"))
      (node (ref "R8") (pin "2") (pinfunction "2_2") (pintype "passive"))
    )
    (net (code "94") (name "Net-(J11-2)") (class "Default")
      (node (ref "J11") (pin "P2") (pinfunction "2_P2") (pintype "passive"))
      (node (ref "R62") (pin "1") (pinfunction "1_1") (pintype "passive"))
    )
    (net (code "95") (name "Net-(J11-3)") (class "Default")
      (node (ref "J11") (pin "P3") (pinfunction "3_P3") (pintype "passive"))
      (node (ref "R6") (pin "2") (pinfunction "2_2") (pintype "passive"))
    )
    (net (code "96") (name "Net-(J12-2)") (class "Default")
      (node (ref "J12") (pin "P2") (pinfunction "2_P2") (pintype "passive"))
      (node (ref "R64") (pin "1") (pinfunction "1_1") (pintype "passive"))
    )
    (net (code "97") (name "Net-(J12-3)") (class "Default")
      (node (ref "J12") (pin "P3") (pinfunction "3_P3") (pintype "passive"))
      (node (ref "R9") (pin "2") (pinfunction "2_2") (pintype "passive"))
    )
    (net (code "98") (name "Net-(JP1-Pad10)") (class "Default")
      (node (ref "JP1") (pin "10") (pinfunction "10_10") (pintype "passive"))
      (node (ref "JP1") (pin "9") (pinfunction "9_9") (pintype "passive"))
      (node (ref "P1") (pin "2") (pinfunction "2_2") (pintype "bidirectional"))
    )
    (net (code "99") (name "Net-(L1-Pad2)") (class "Default")
      (node (ref "L1") (pin "2") (pinfunction "2_2") (pintype "passive"))
      (node (ref "P1") (pin "1") (pinfunction "1_1") (pintype "bidirectional"))
    )
    (net (code "100") (name "Net-(R98A-A)") (class "Default")
      (node (ref "D6") (pin "C") (pinfunction "C_C") (pintype "passive"))
      (node (ref "R81") (pin "2") (pinfunction "2_2") (pintype "passive"))
      (node (ref "R98") (pin "B") (pinfunction "A_B") (pintype "passive"))
    )
    (net (code "101") (name "Net-(R98A-C)") (class "Default")
      (node (ref "D6") (pin "A") (pinfunction "A_A") (pintype "passive"))
      (node (ref "R13") (pin "1") (pinfunction "1_1") (pintype "passive"))
      (node (ref "R73") (pin "2") (pinfunction "2_2") (pintype "passive"))
      (node (ref "R98") (pin "E") (pinfunction "C_E") (pintype "passive"))
    )
    (net (code "102") (name "Net-(R98B-S)") (class "Default")
      (node (ref "R7") (pin "1") (pinfunction "1_1") (pintype "passive"))
      (node (ref "R98") (pin "2") (pinfunction "S_2") (pintype "passive"))
    )
    (net (code "103") (name "Net-(R99A-A)") (class "Default")
      (node (ref "D5") (pin "C") (pinfunction "C_C") (pintype "passive"))
      (node (ref "R79") (pin "2") (pinfunction "2_2") (pintype "passive"))
      (node (ref "R99") (pin "B") (pinfunction "A_B") (pintype "passive"))
    )
    (net (code "104") (name "Net-(R99A-C)") (class "Default")
      (node (ref "D5") (pin "A") (pinfunction "A_A") (pintype "passive"))
      (node (ref "R12") (pin "1") (pinfunction "1_1") (pintype "passive"))
      (node (ref "R72") (pin "2") (pinfunction "2_2") (pintype "passive"))
      (node (ref "R99") (pin "E") (pinfunction "C_E") (pintype "passive"))
    )
    (net (code "105") (name "Net-(R99B-S)") (class "Default")
      (node (ref "R8") (pin "1") (pinfunction "1_1") (pintype "passive"))
      (node (ref "R99") (pin "2") (pinfunction "S_2") (pintype "passive"))
    )
    (net (code "106") (name "Net-(R100A-A)") (class "Default")
      (node (ref "D4") (pin "C") (pinfunction "C_C") (pintype "passive"))
      (node (ref "R100") (pin "B") (pinfunction "A_B") (pintype "passive"))
      (node (ref "R78") (pin "2") (pinfunction "2_2") (pintype "passive"))
    )
    (net (code "107") (name "Net-(R100A-C)") (class "Default")
      (node (ref "D4") (pin "A") (pinfunction "A_A") (pintype "passive"))
      (node (ref "R10") (pin "1") (pinfunction "1_1") (pintype "passive"))
      (node (ref "R100") (pin "E") (pinfunction "C_E") (pintype "passive"))
      (node (ref "R70") (pin "2") (pinfunction "2_2") (pintype "passive"))
    )
    (net (code "108") (name "Net-(R100B-S)") (class "Default")
      (node (ref "R100") (pin "2") (pinfunction "S_2") (pintype "passive"))
      (node (ref "R6") (pin "1") (pinfunction "1_1") (pintype "passive"))
    )
    (net (code "109") (name "Net-(R101A-A)") (class "Default")
      (node (ref "D3") (pin "C") (pinfunction "C_C") (pintype "passive"))
      (node (ref "R101") (pin "B") (pinfunction "A_B") (pintype "passive"))
      (node (ref "R80") (pin "2") (pinfunction "2_2") (pintype "passive"))
    )
    (net (code "110") (name "Net-(R101A-C)") (class "Default")
      (node (ref "D3") (pin "A") (pinfunction "A_A") (pintype "passive"))
      (node (ref "R101") (pin "E") (pinfunction "C_E") (pintype "passive"))
      (node (ref "R11") (pin "1") (pinfunction "1_1") (pintype "passive"))
      (node (ref "R71") (pin "2") (pinfunction "2_2") (pintype "passive"))
    )
    (net (code "111") (name "Net-(R101B-S)") (class "Default")
      (node (ref "R101") (pin "2") (pinfunction "S_2") (pintype "passive"))
      (node (ref "R9") (pin "1") (pinfunction "1_1") (pintype "passive"))
    )
    (net (code "112") (name "Net-(R102-S)") (class "Default")
      (node (ref "C4") (pin "1") (pinfunction "1_1") (pintype "passive"))
      (node (ref "R102") (pin "P$2") (pinfunction "S_P$2") (pintype "passive"))
      (node (ref "R15") (pin "2") (pinfunction "2_2") (pintype "passive"))
    )
    (net (code "113") (name "Net-(R103-S)") (class "Default")
      (node (ref "C5") (pin "1") (pinfunction "1_1") (pintype "passive"))
      (node (ref "R103") (pin "P$2") (pinfunction "S_P$2") (pintype "passive"))
      (node (ref "R16") (pin "2") (pinfunction "2_2") (pintype "passive"))
    )
    (net (code "114") (name "Net-(R104-S)") (class "Default")
      (node (ref "C2") (pin "1") (pinfunction "1_1") (pintype "passive"))
      (node (ref "R104") (pin "P$2") (pinfunction "S_P$2") (pintype "passive"))
      (node (ref "R17") (pin "2") (pinfunction "2_2") (pintype "passive"))
    )
    (net (code "115") (name "Net-(R105-S)") (class "Default")
      (node (ref "C3") (pin "1") (pinfunction "1_1") (pintype "passive"))
      (node (ref "R105") (pin "P$2") (pinfunction "S_P$2") (pintype "passive"))
      (node (ref "R14") (pin "2") (pinfunction "2_2") (pintype "passive"))
    )
    (net (code "116") (name "Net-(R106-A)") (class "Default")
      (node (ref "R106") (pin "P$3") (pinfunction "A_P$3") (pintype "passive"))
      (node (ref "R4") (pin "2") (pinfunction "2_2") (pintype "passive"))
    )
    (net (code "117") (name "Net-(R107-A)") (class "Default")
      (node (ref "R107") (pin "P$3") (pinfunction "A_P$3") (pintype "passive"))
      (node (ref "R3") (pin "2") (pinfunction "2_2") (pintype "passive"))
    )
    (net (code "118") (name "Net-(R108-A)") (class "Default")
      (node (ref "R108") (pin "P$3") (pinfunction "A_P$3") (pintype "passive"))
      (node (ref "R2") (pin "2") (pinfunction "2_2") (pintype "passive"))
    )
    (net (code "119") (name "Net-(R109-A)") (class "Default")
      (node (ref "R1") (pin "2") (pinfunction "2_2") (pintype "passive"))
      (node (ref "R109") (pin "P$3") (pinfunction "A_P$3") (pintype "passive"))
    )
    (net (code "120") (name "VCC") (class "Default")
      (node (ref "C10") (pin "1") (pinfunction "1_1") (pintype "passive"))
      (node (ref "C11") (pin "1") (pinfunction "1_1") (pintype "passive"))
      (node (ref "C18") (pin "1") (pinfunction "1_1") (pintype "passive"))
      (node (ref "C19") (pin "1") (pinfunction "1_1") (pintype "passive"))
      (node (ref "C34") (pin "1") (pinfunction "1_1") (pintype "passive"))
      (node (ref "C35") (pin "1") (pinfunction "1_1") (pintype "passive"))
      (node (ref "C36") (pin "1") (pinfunction "1_1") (pintype "passive"))
      (node (ref "C37") (pin "1") (pinfunction "1_1") (pintype "passive"))
      (node (ref "C43") (pin "1") (pinfunction "1_1") (pintype "passive"))
      (node (ref "C45") (pin "1") (pinfunction "1_1") (pintype "passive"))
      (node (ref "C48") (pin "1") (pinfunction "1_1") (pintype "passive"))
      (node (ref "C50") (pin "1") (pinfunction "1_1") (pintype "passive"))
      (node (ref "IC10") (pin "4") (pinfunction "V+_4") (pintype "power_in"))
      (node (ref "IC2") (pin "4") (pinfunction "V+_4") (pintype "power_in"))
      (node (ref "IC3") (pin "4") (pinfunction "V+_4") (pintype "power_in"))
      (node (ref "IC4") (pin "16") (pinfunction "V+_16") (pintype "power_in"))
      (node (ref "IC5") (pin "16") (pinfunction "V+_16") (pintype "power_in"))
      (node (ref "IC6") (pin "4") (pinfunction "V+_4") (pintype "power_in"))
      (node (ref "IC7") (pin "4") (pinfunction "V+_4") (pintype "power_in"))
      (node (ref "IC9") (pin "4") (pinfunction "V+_4") (pintype "power_in"))
      (node (ref "L2") (pin "1") (pinfunction "1_1") (pintype "passive"))
      (node (ref "R33") (pin "1") (pinfunction "1_1") (pintype "passive"))
      (node (ref "R34") (pin "1") (pinfunction "1_1") (pintype "passive"))
      (node (ref "R69") (pin "1") (pinfunction "1_1") (pintype "passive"))
    )
    (net (code "121") (name "VEE") (class "Default")
      (node (ref "C12") (pin "2") (pinfunction "2_2") (pintype "passive"))
      (node (ref "C13") (pin "2") (pinfunction "2_2") (pintype "passive"))
      (node (ref "C26") (pin "2") (pinfunction "2_2") (pintype "passive"))
      (node (ref "C29") (pin "2") (pinfunction "2_2") (pintype "passive"))
      (node (ref "C38") (pin "2") (pinfunction "2_2") (pintype "passive"))
      (node (ref "C39") (pin "2") (pinfunction "2_2") (pintype "passive"))
      (node (ref "C44") (pin "2") (pinfunction "2_2") (pintype "passive"))
      (node (ref "C46") (pin "2") (pinfunction "2_2") (pintype "passive"))
      (node (ref "C47") (pin "2") (pinfunction "2_2") (pintype "passive"))
      (node (ref "C49") (pin "2") (pinfunction "2_2") (pintype "passive"))
      (node (ref "C6") (pin "2") (pinfunction "2_2") (pintype "passive"))
      (node (ref "C7") (pin "2") (pinfunction "2_2") (pintype "passive"))
      (node (ref "D1") (pin "A") (pinfunction "A_A") (pintype "passive"))
      (node (ref "IC10") (pin "11") (pinfunction "V-_11") (pintype "power_in"))
      (node (ref "IC2") (pin "11") (pinfunction "V-_11") (pintype "power_in"))
      (node (ref "IC3") (pin "11") (pinfunction "V-_11") (pintype "power_in"))
      (node (ref "IC4") (pin "9") (pinfunction "V-_9") (pintype "power_in"))
      (node (ref "IC5") (pin "9") (pinfunction "V-_9") (pintype "power_in"))
      (node (ref "IC6") (pin "11") (pinfunction "V-_11") (pintype "power_in"))
      (node (ref "IC7") (pin "11") (pinfunction "V-_11") (pintype "power_in"))
      (node (ref "IC9") (pin "11") (pinfunction "V-_11") (pintype "power_in"))
      (node (ref "L1") (pin "1") (pinfunction "1_1") (pintype "passive"))
      (node (ref "R5") (pin "1") (pinfunction "1_1") (pintype "passive"))
    )
    (net (code "122") (name "unconnected-(J4-2-PadP2)") (class "Default")
      (node (ref "J4") (pin "P2") (pinfunction "2_P2") (pintype "passive"))
    )
  )
)
